# Flightcontroller.net
KiCad netlist of a schematic drawn in EAGLE
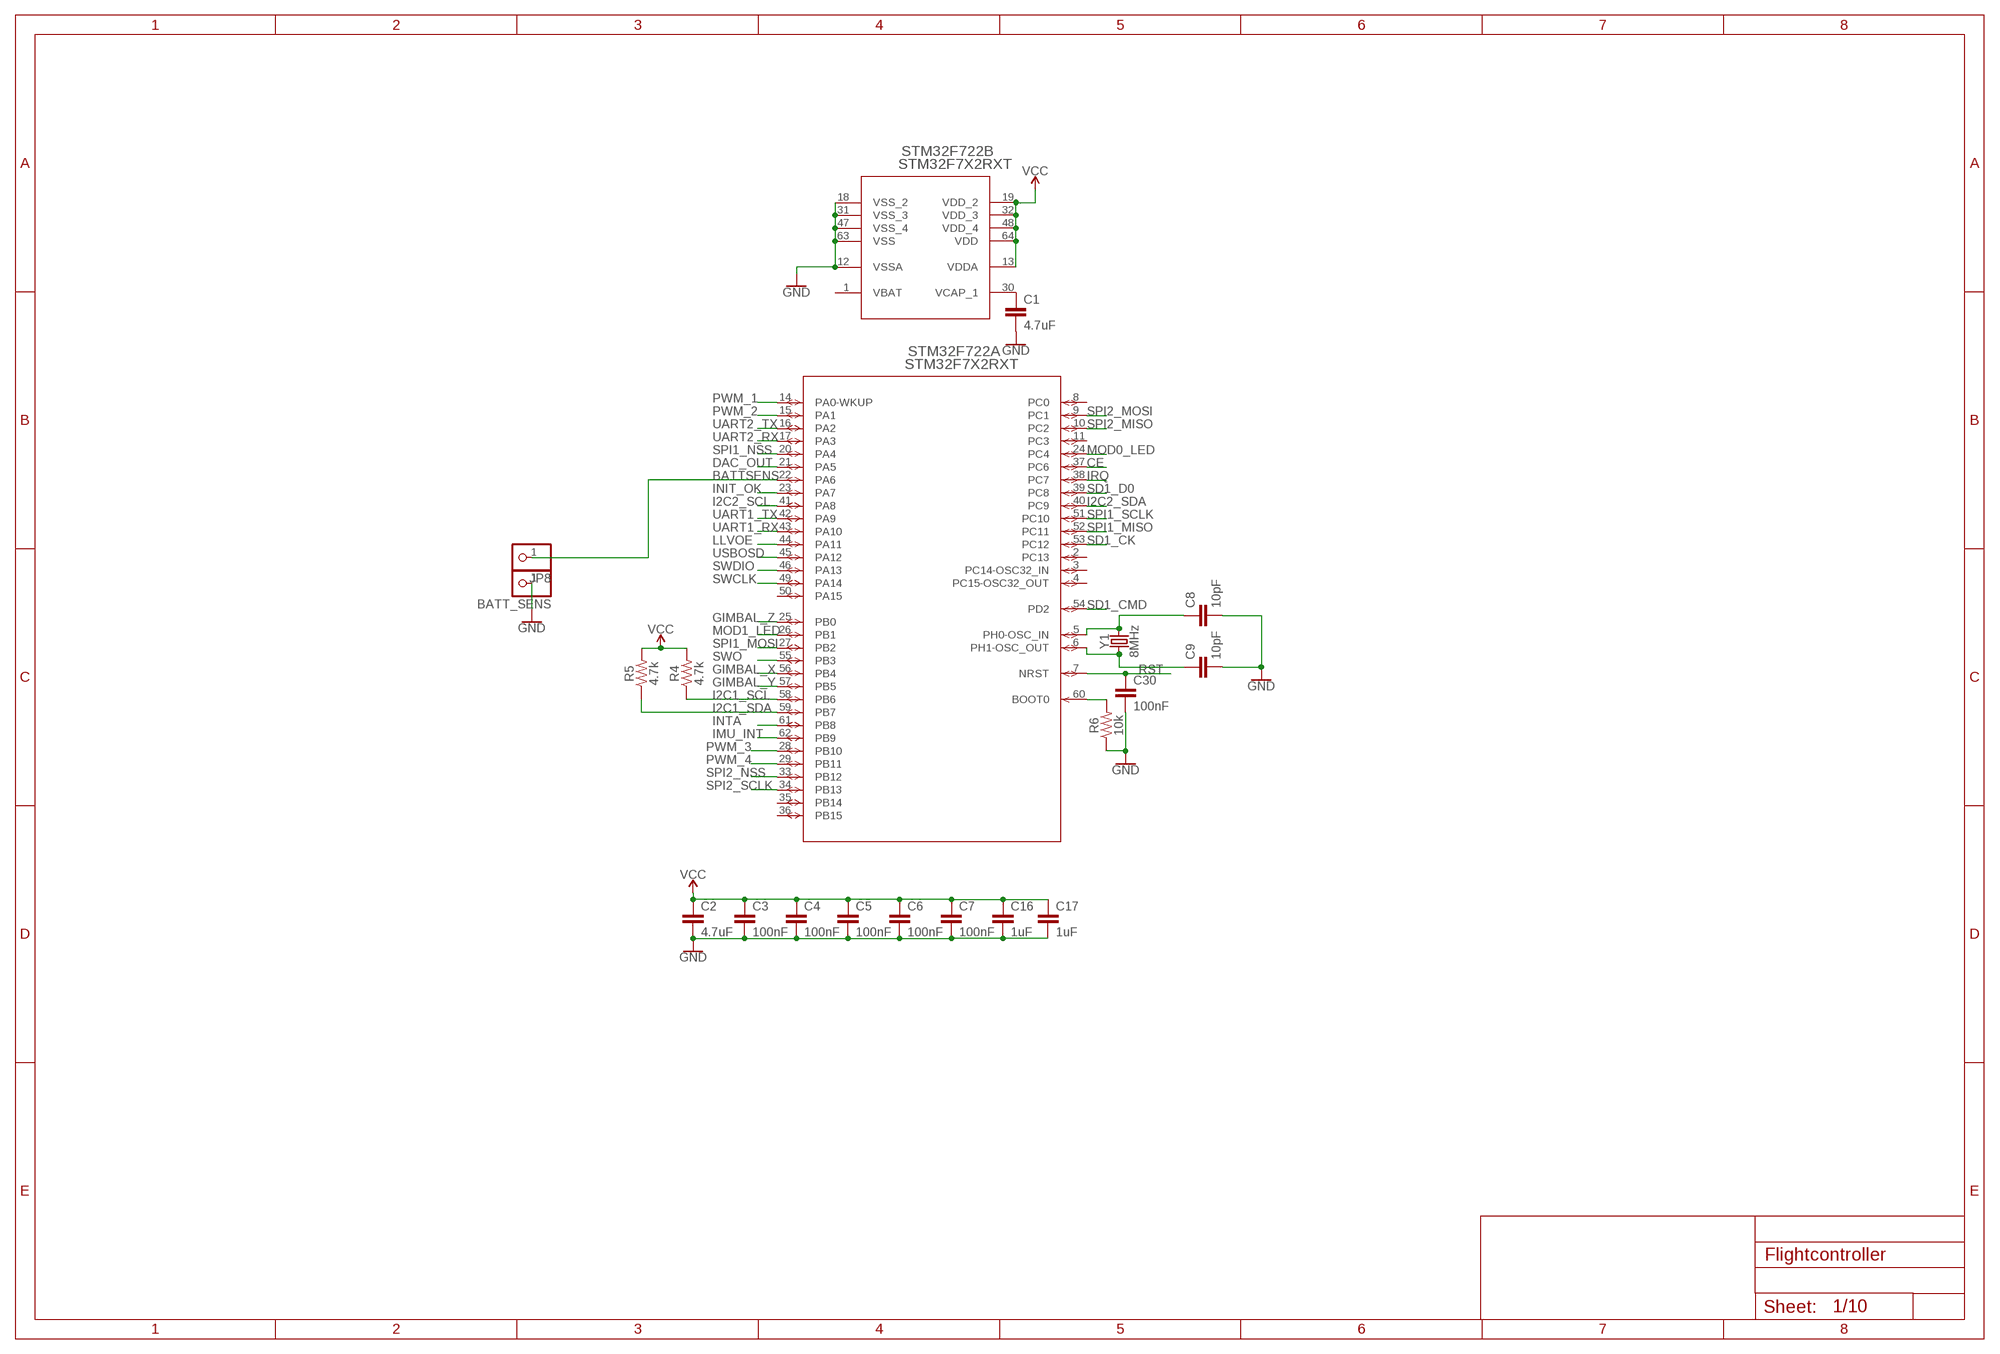
[diagram p0: schematic, sheet 1]
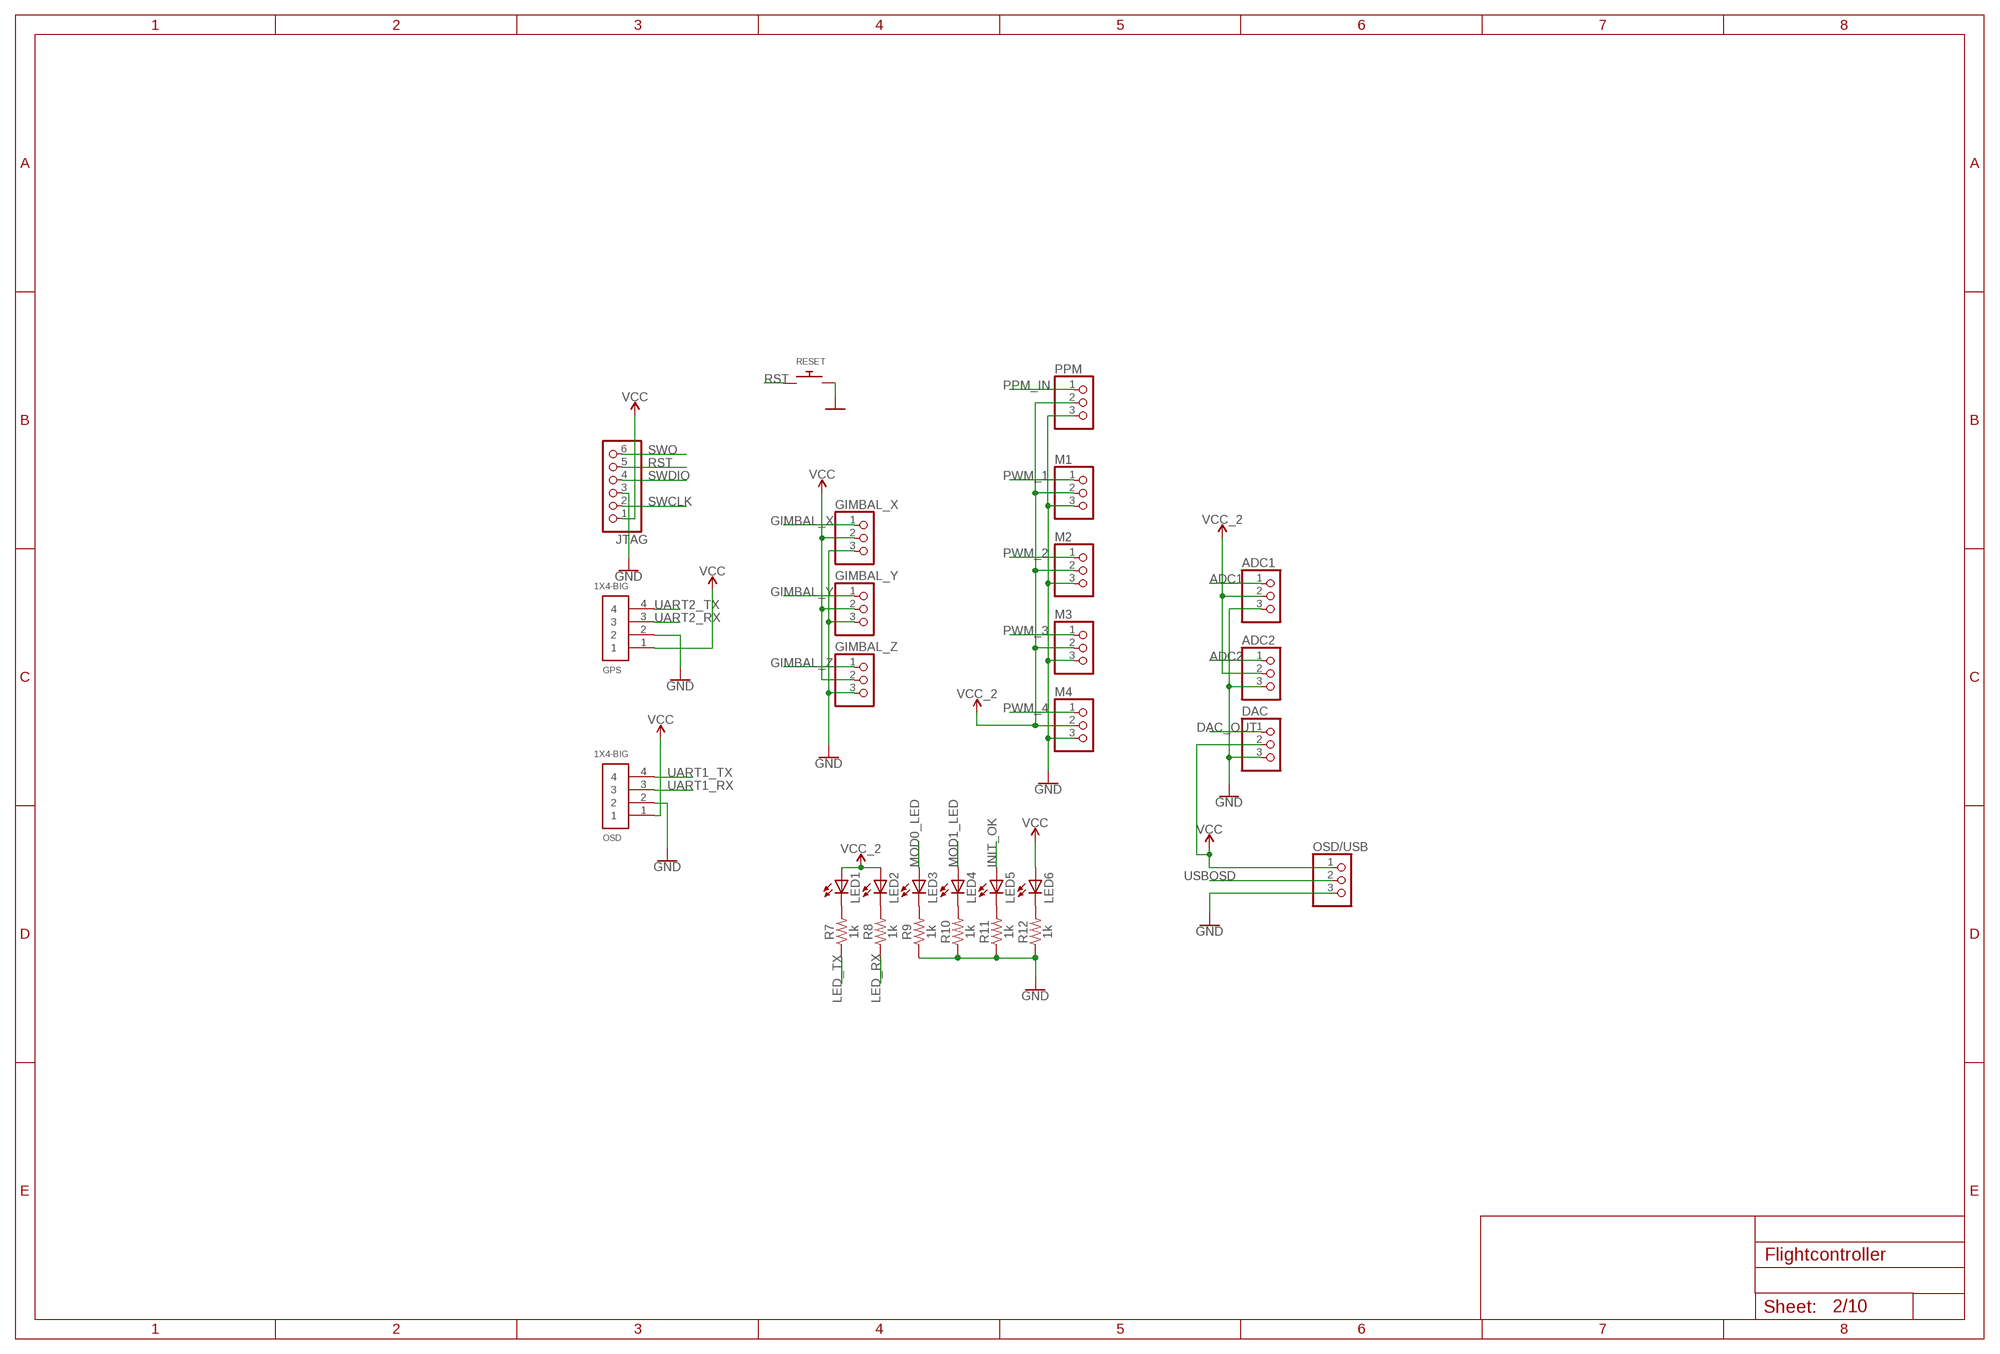
[diagram p1: schematic, sheet 2]
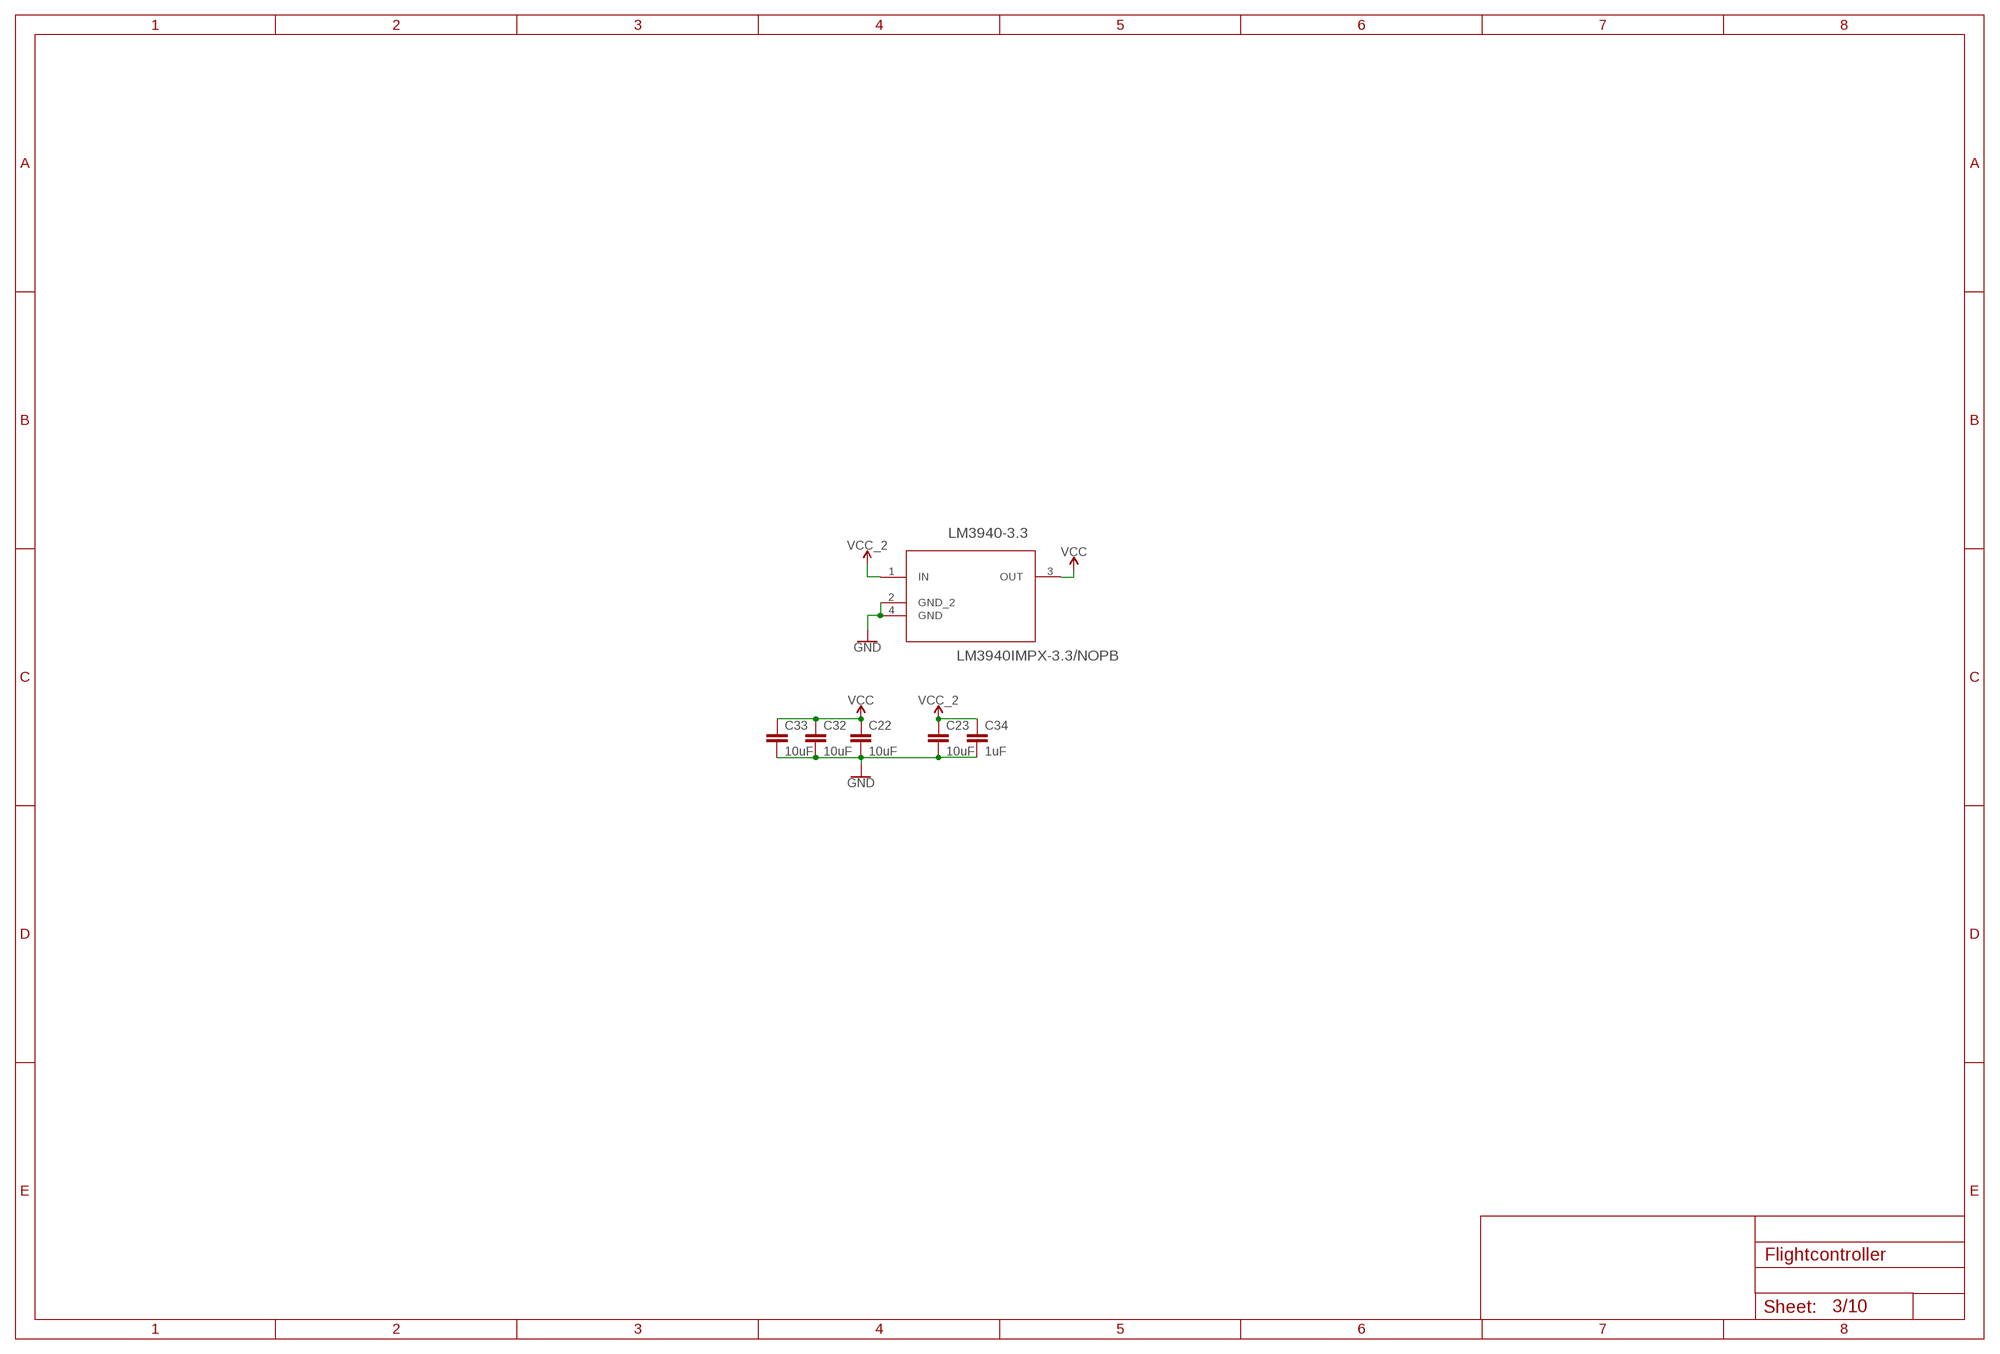
[diagram p2: schematic, sheet 3]
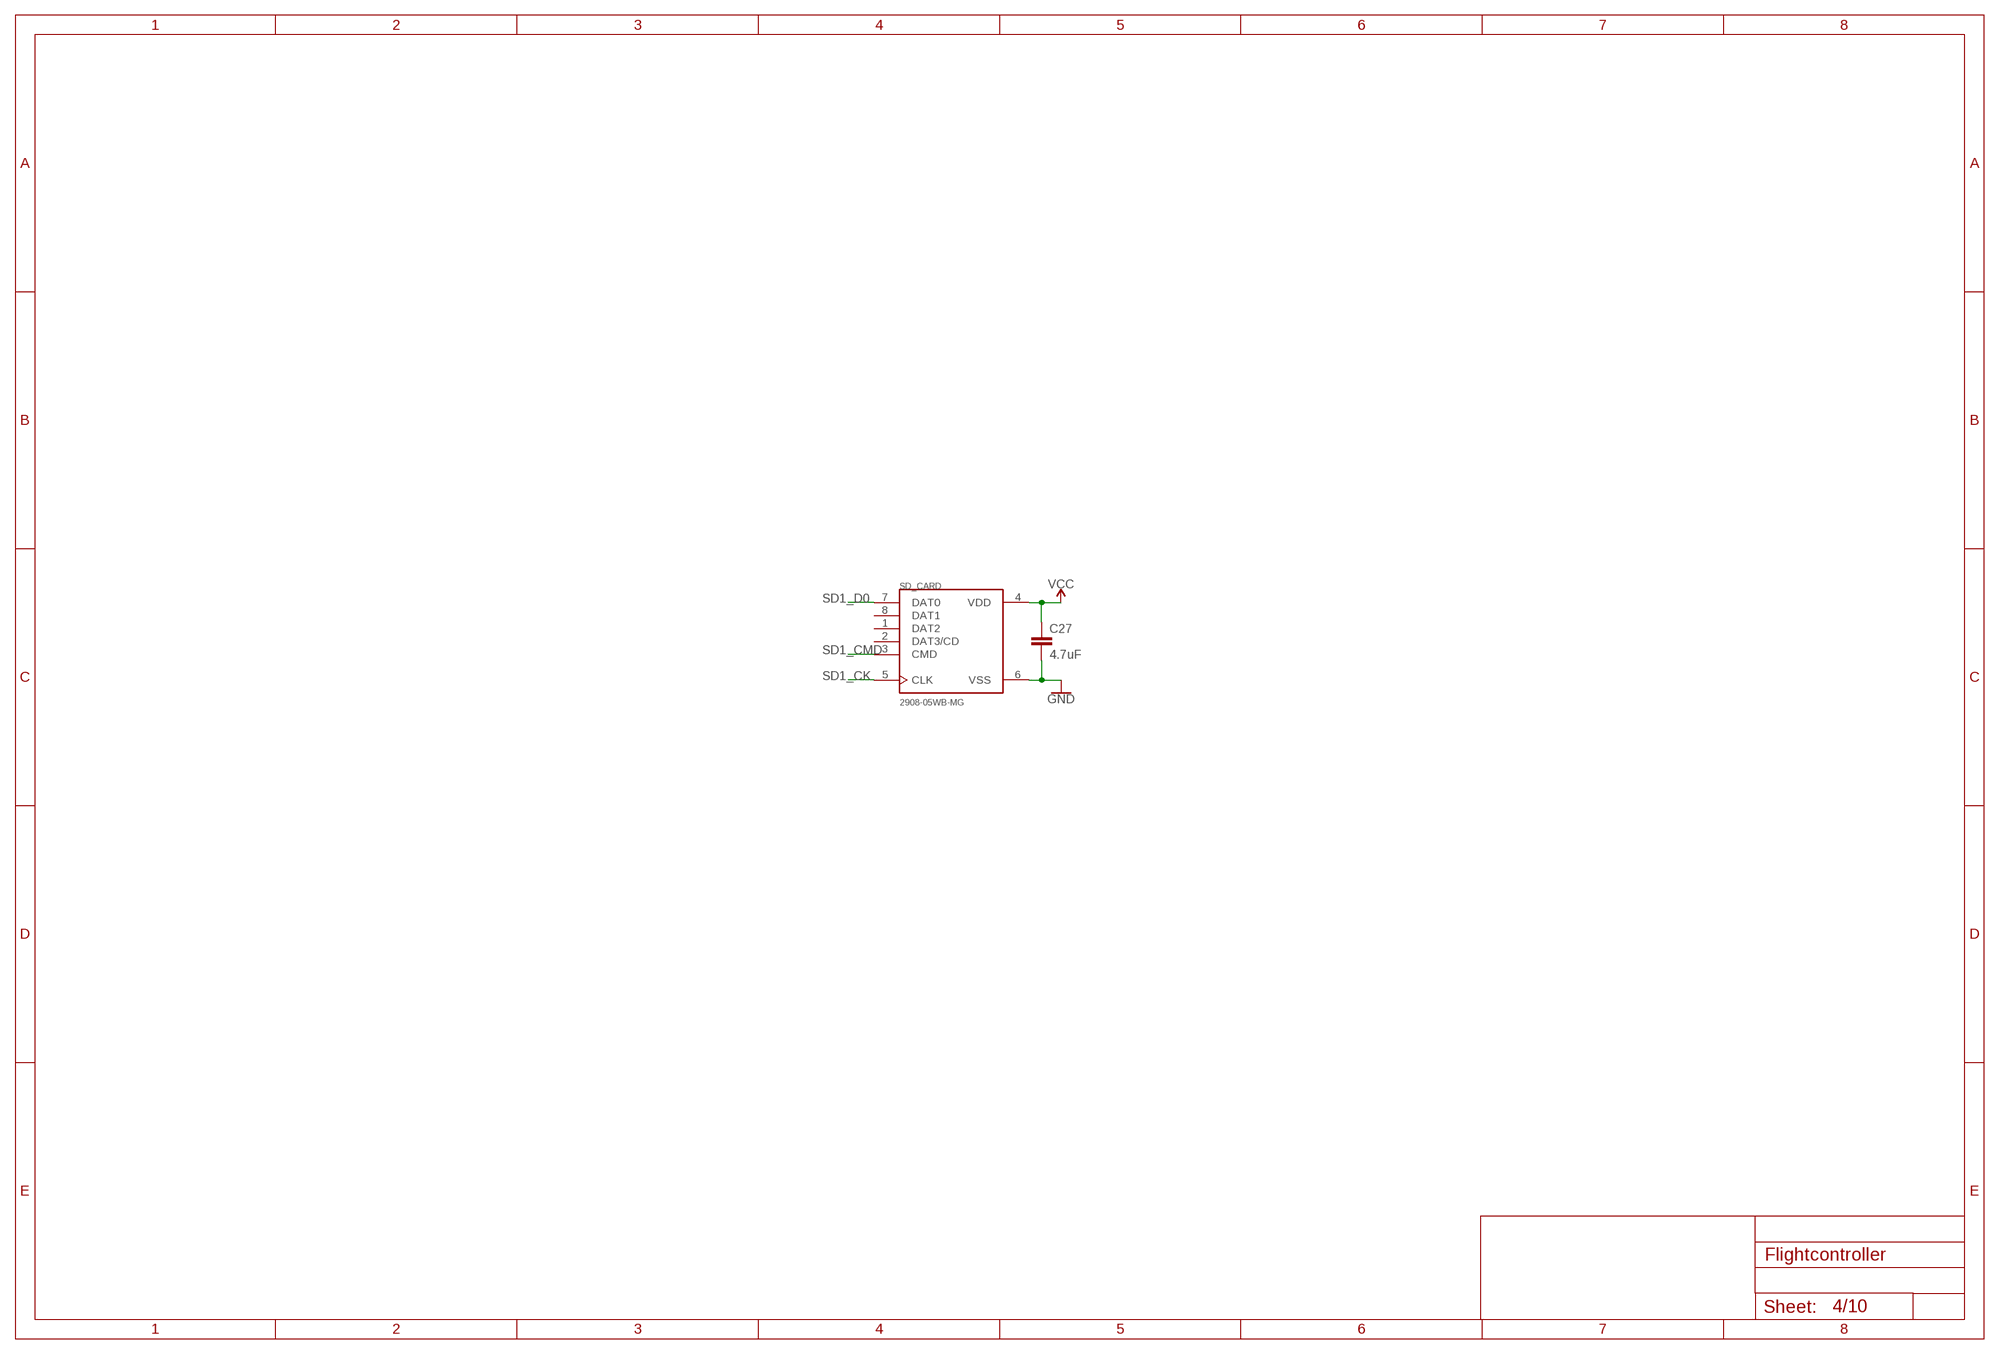
[diagram p3: schematic, sheet 4]
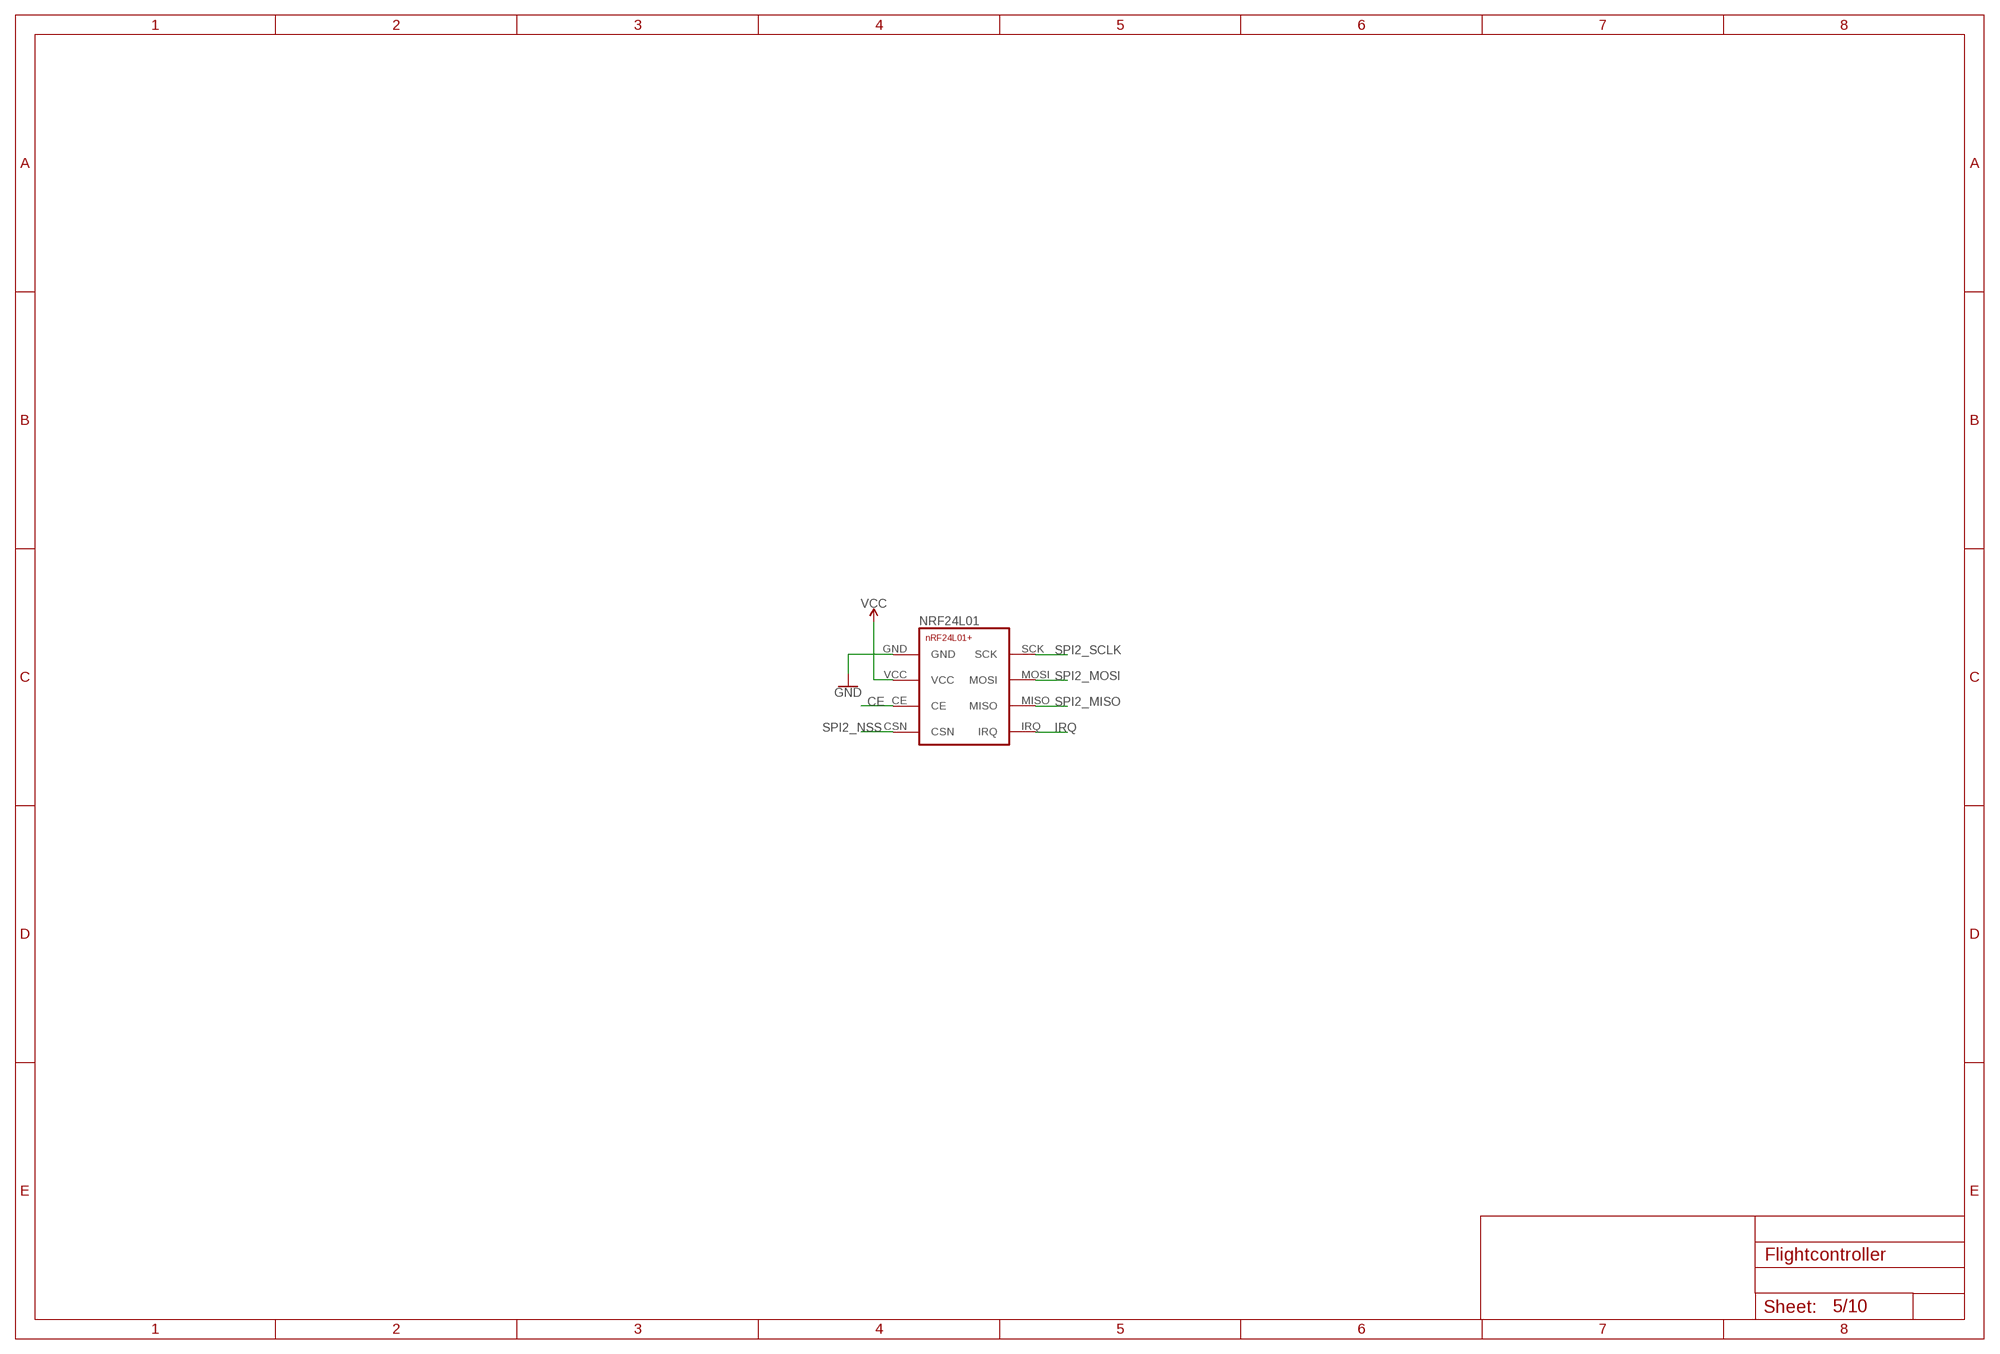
[diagram p4: schematic, sheet 5]
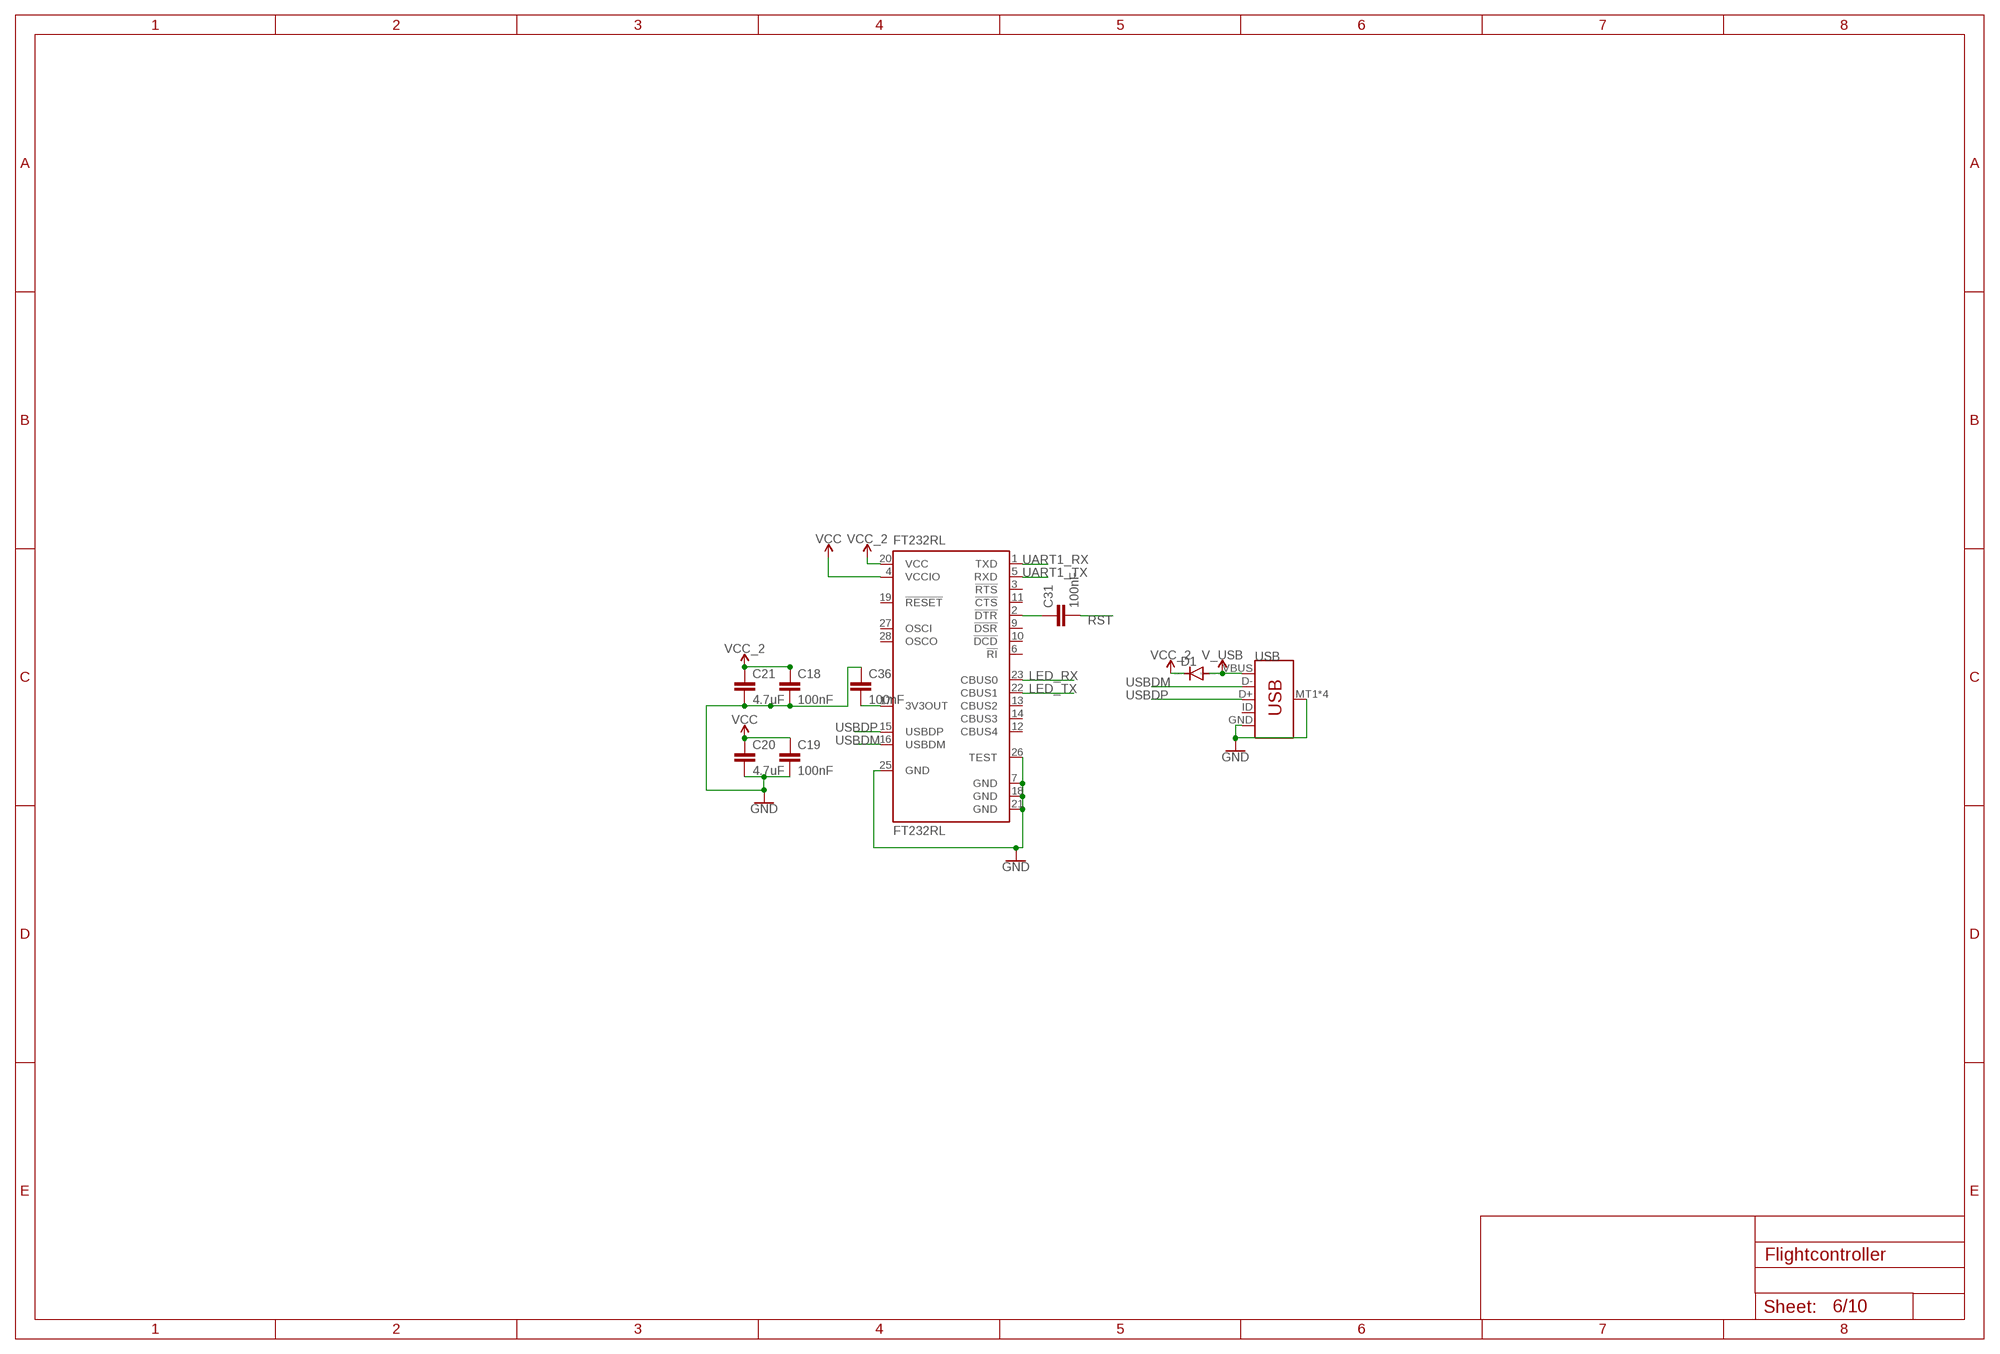
[diagram p5: schematic, sheet 6]
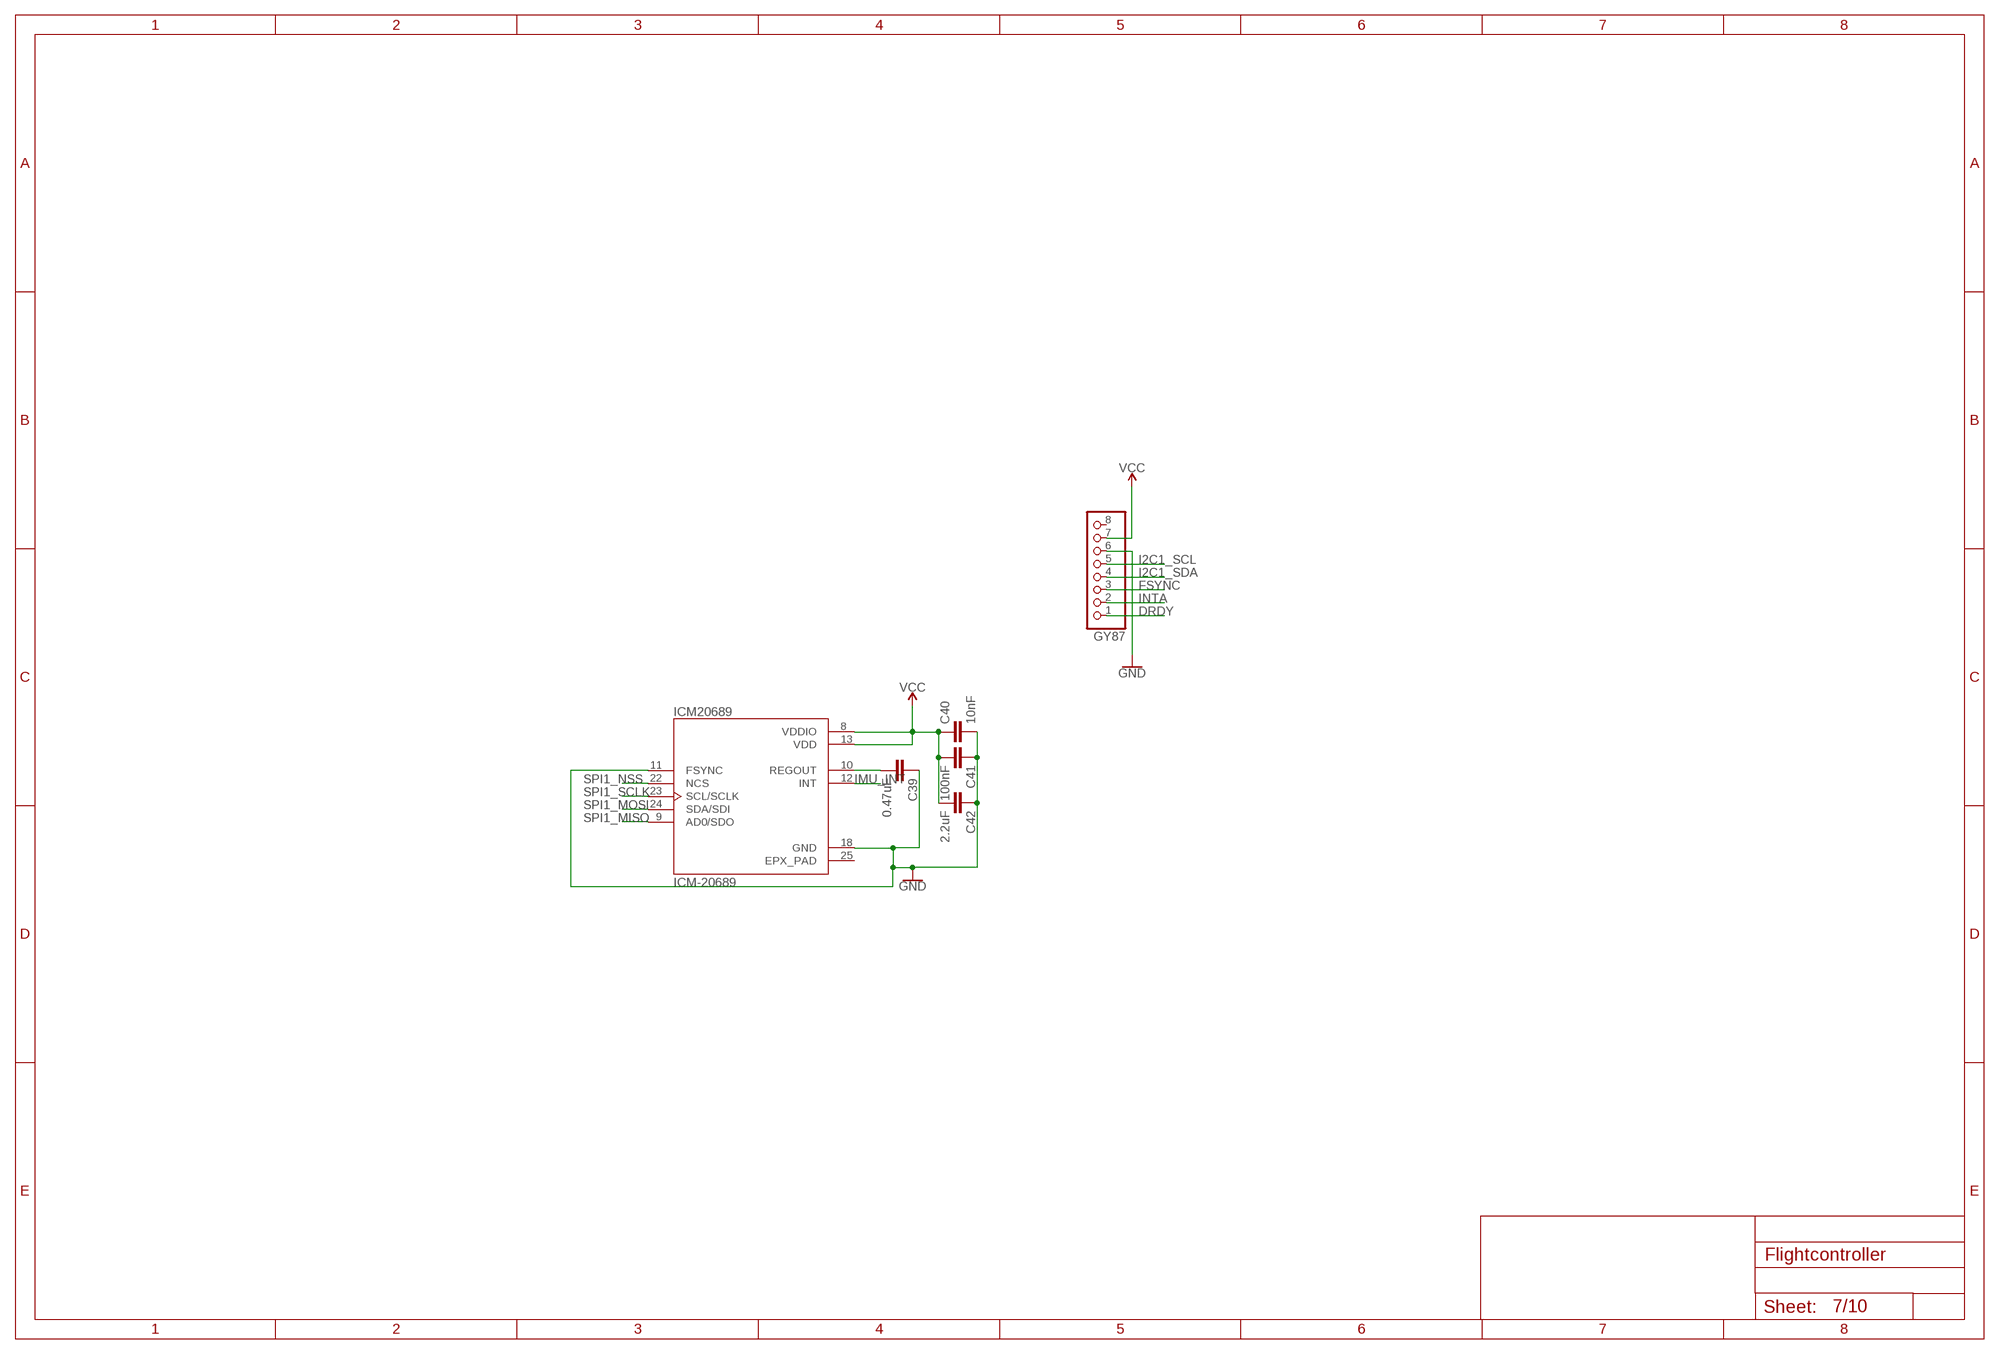
[diagram p6: schematic, sheet 7]
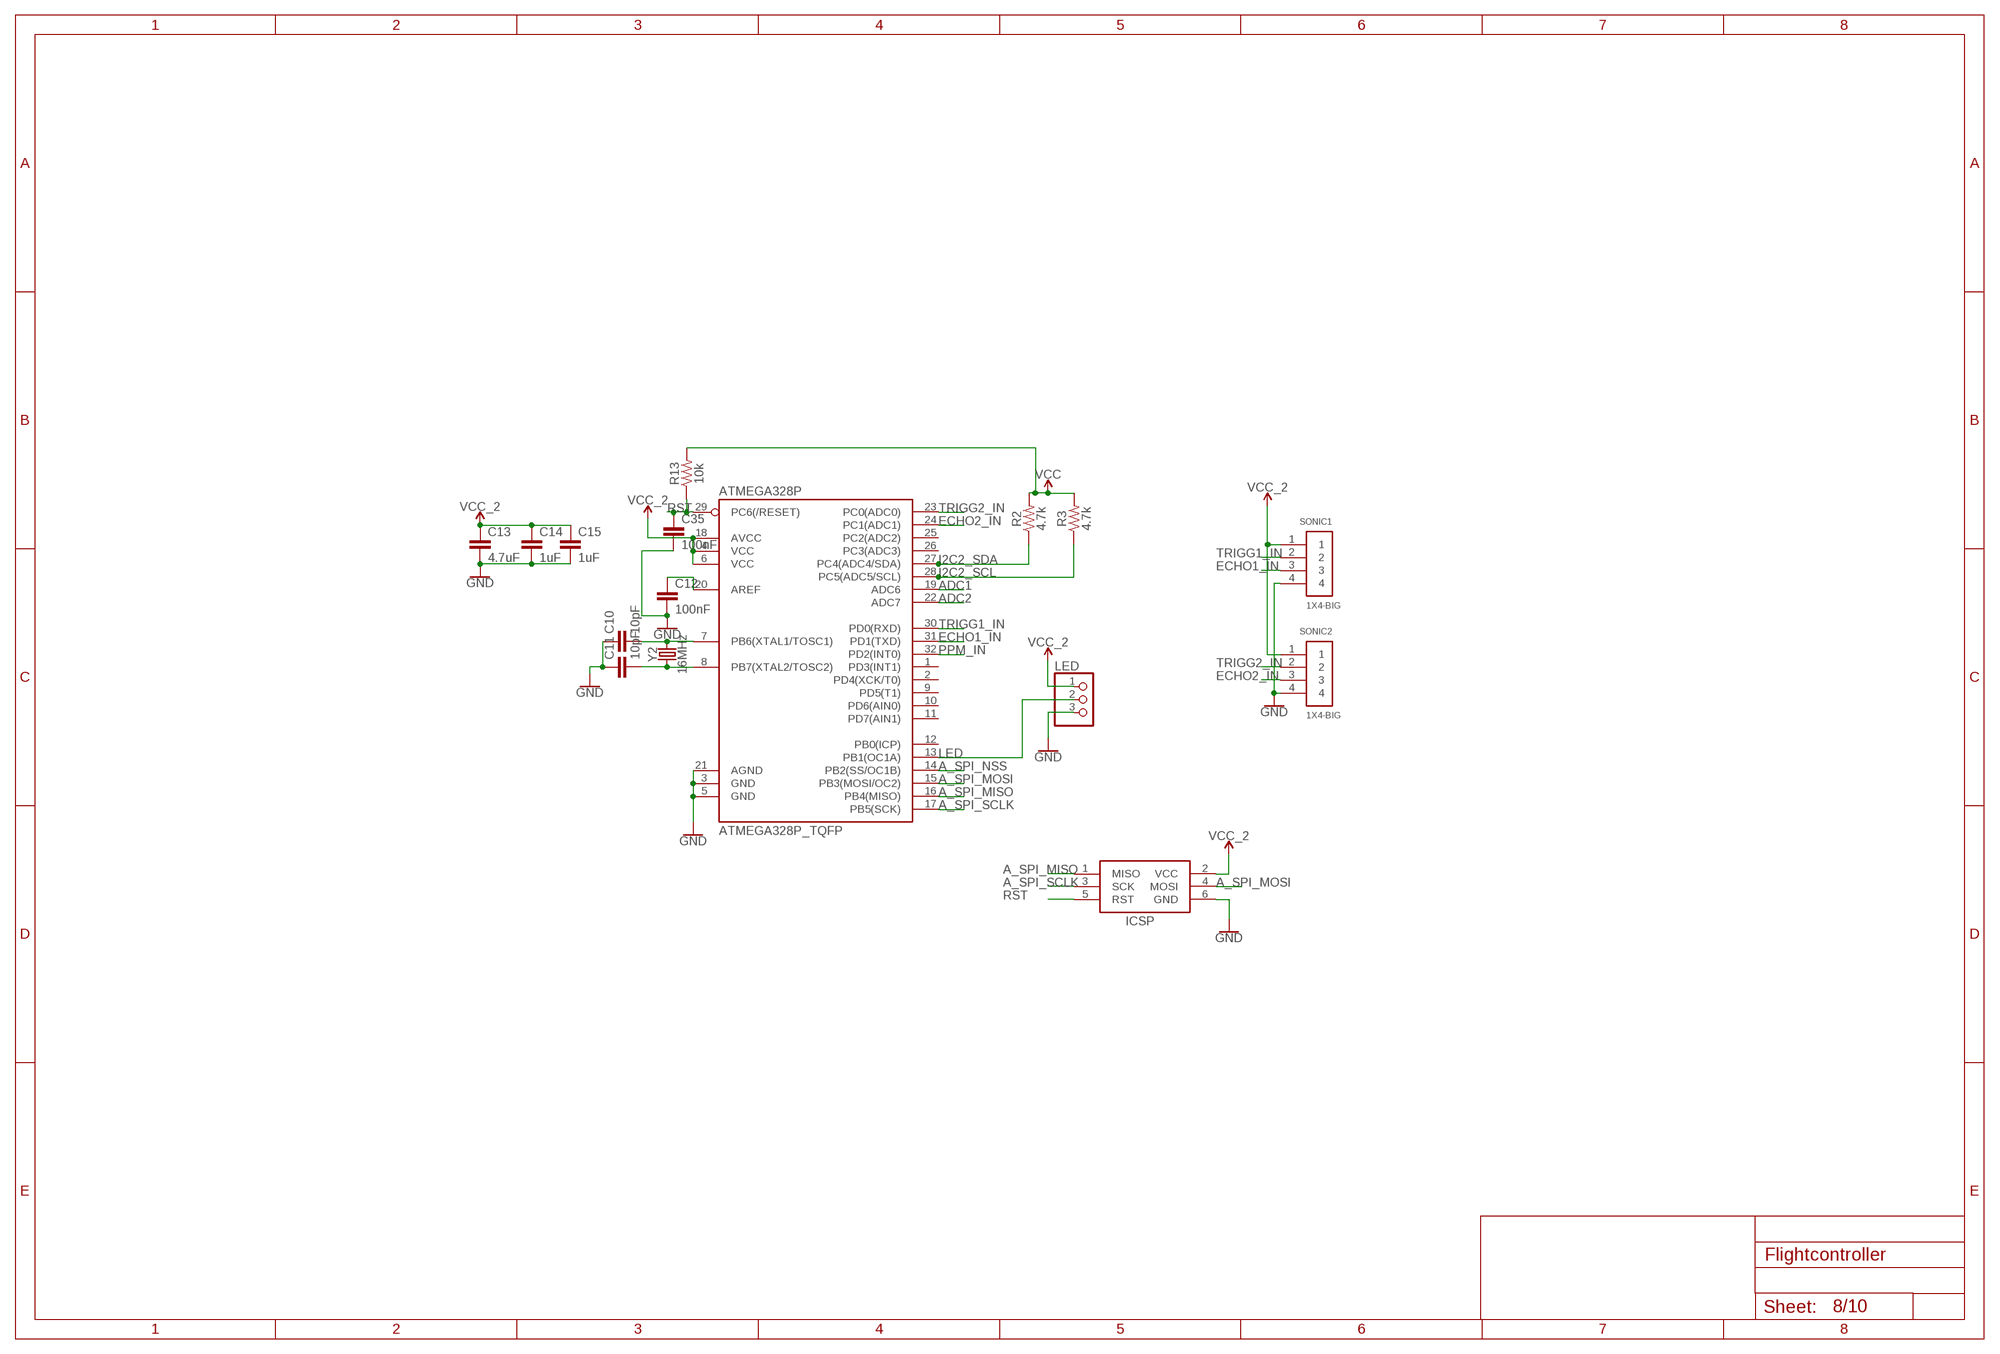
[diagram p7: schematic, sheet 8]
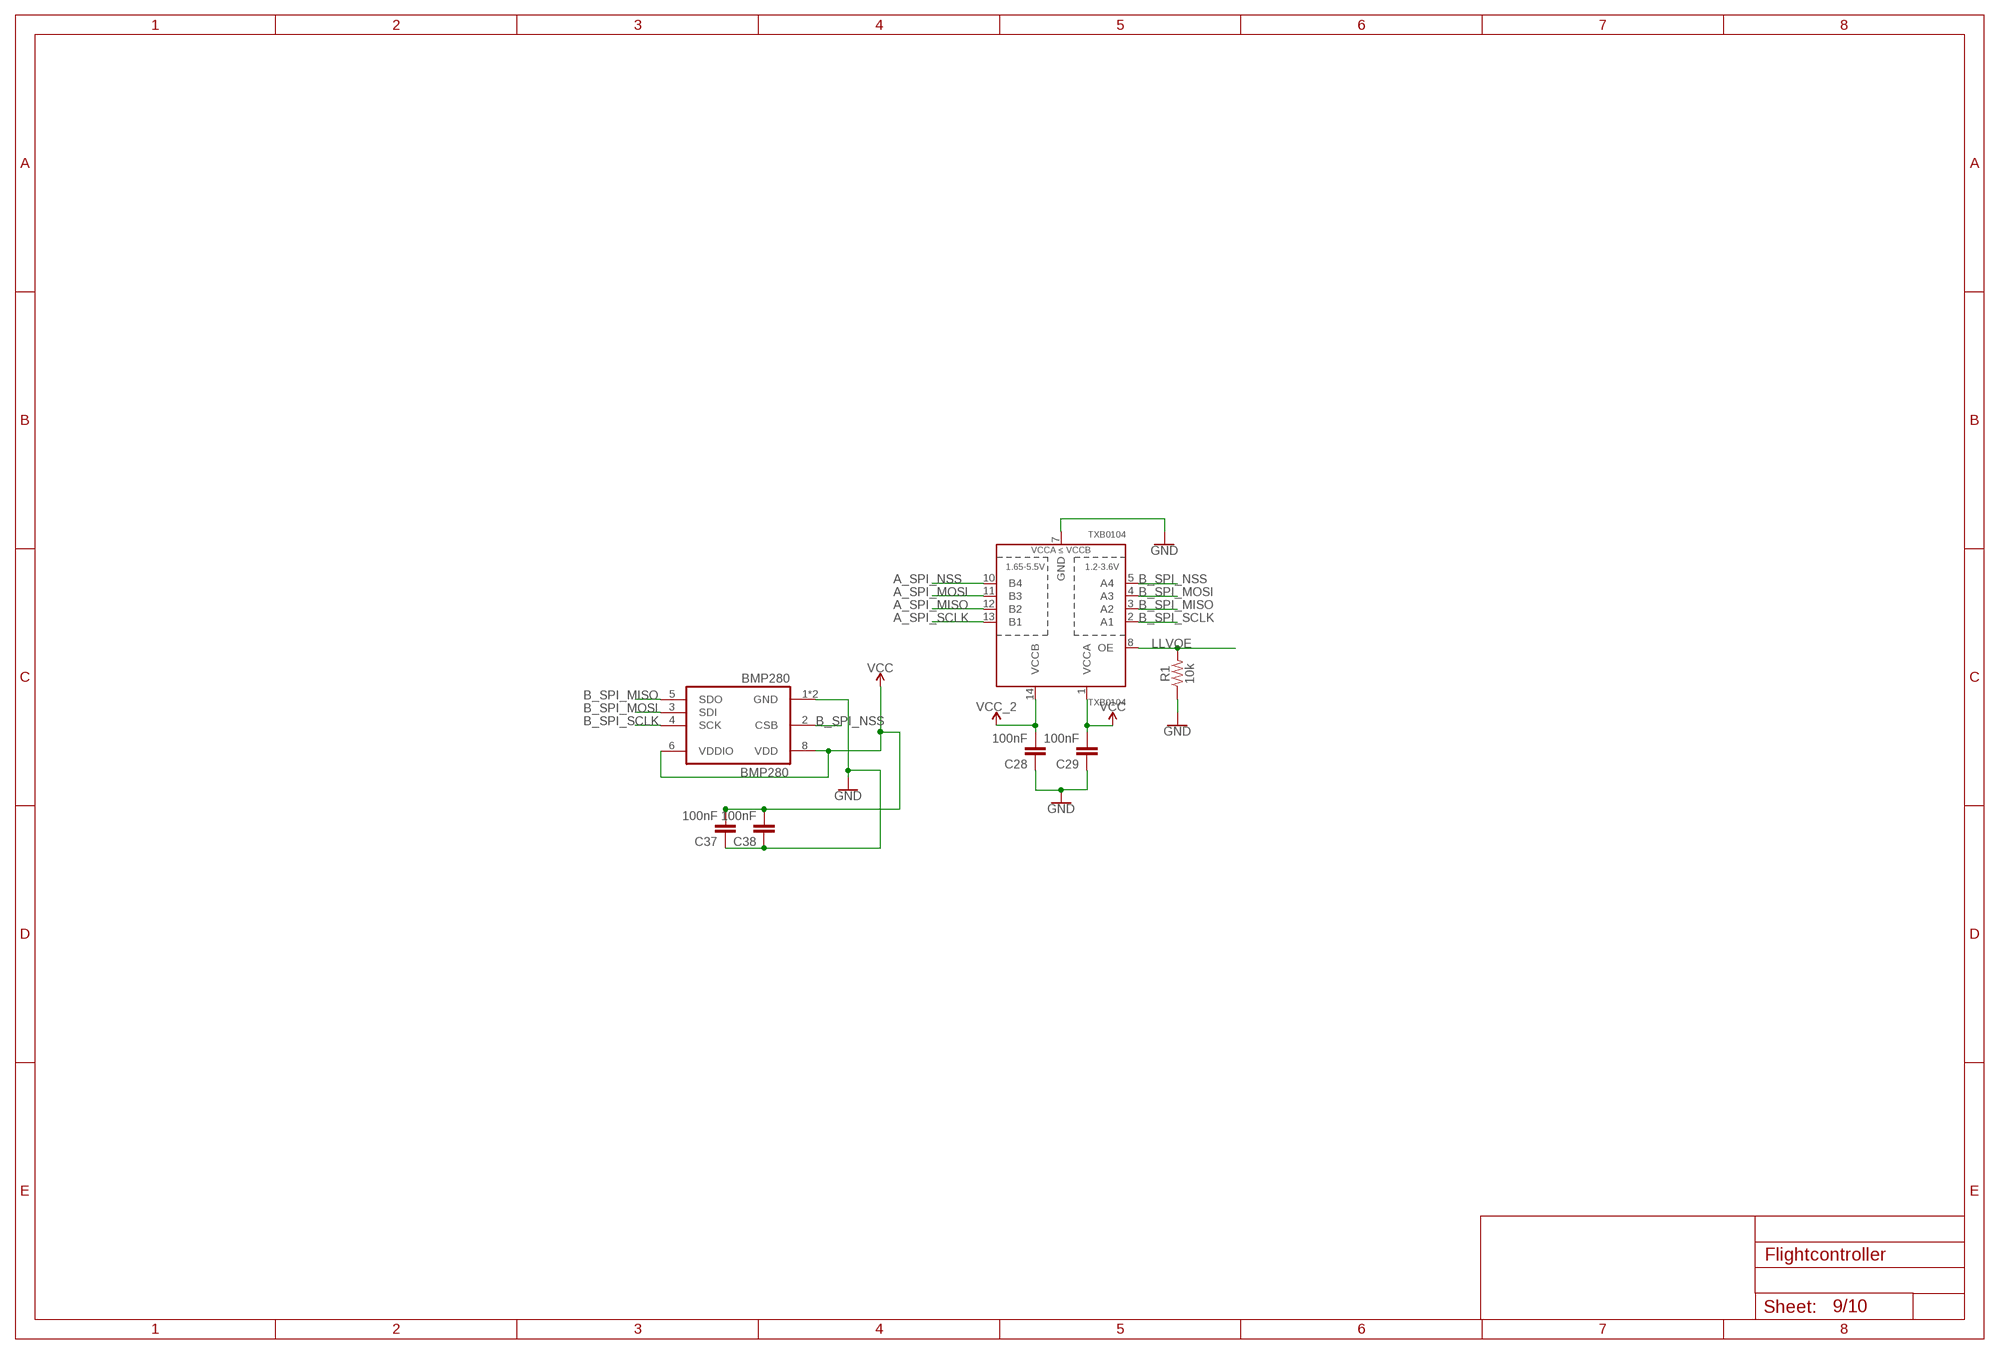
[diagram p8: schematic, sheet 9]
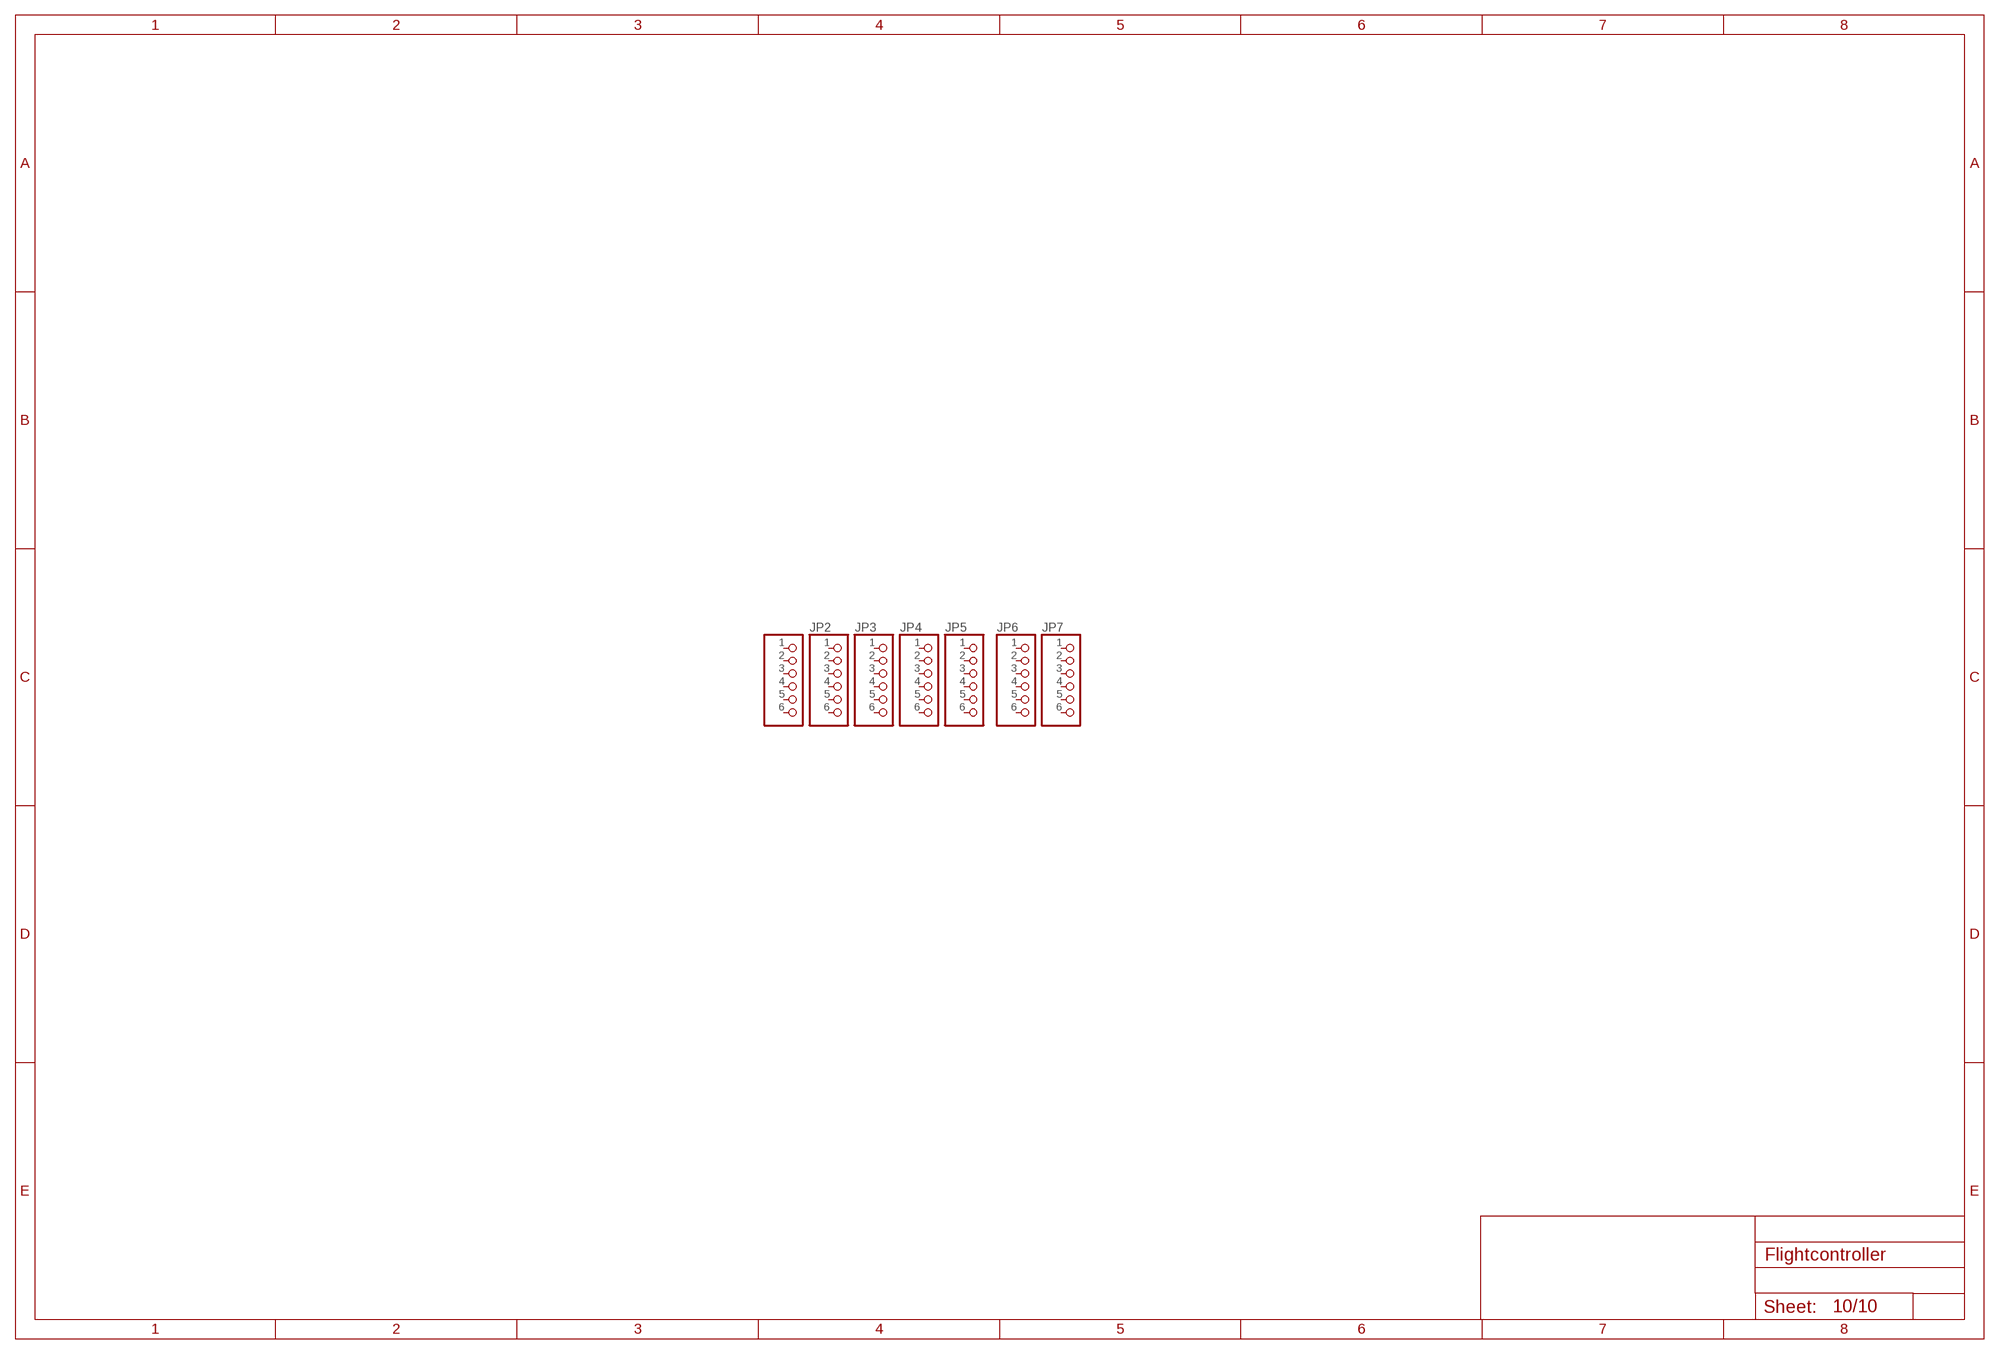
[diagram p9: schematic, sheet 10]

(export (version "E")
  (design (tool "Eeschema 10.0.6"))
  (components
    (comp (ref "BMP280")
      (value "BMP280")
      (footprint "eagle-import:BMP280")
      (libsource (lib "eagle-import") (part "BMP280"))
    )
    (comp (ref "C28")
      (value "100nF")
      (footprint "eagle-import:C0805")
      (libsource (lib "eagle-import") (part "C-EUC0805"))
    )
    (comp (ref "C29")
      (value "100nF")
      (footprint "eagle-import:C0805")
      (libsource (lib "eagle-import") (part "C-EUC0805"))
    )
    (comp (ref "C37")
      (value "100nF")
      (footprint "eagle-import:C0805")
      (libsource (lib "eagle-import") (part "C-EUC0805"))
    )
    (comp (ref "C38")
      (value "100nF")
      (footprint "eagle-import:C0805")
      (libsource (lib "eagle-import") (part "C-EUC0805"))
    )
    (comp (ref "R1")
      (value "10k")
      (footprint "eagle-import:0603")
      (libsource (lib "eagle-import") (part "10KOHM-0603-1/10W-1%"))
    )
    (comp (ref "TXB0104")
      (value "TXB0104")
      (footprint "eagle-import:SO14")
      (libsource (lib "eagle-import") (part "TXB0104PWRSOIC14"))
    )
    (comp (ref "C18")
      (value "100nF")
      (footprint "eagle-import:C0805")
      (libsource (lib "eagle-import") (part "C-EUC0805"))
    )
    (comp (ref "C19")
      (value "100nF")
      (footprint "eagle-import:C0805")
      (libsource (lib "eagle-import") (part "C-EUC0805"))
    )
    (comp (ref "C20")
      (value "4.7uF")
      (footprint "eagle-import:C0805")
      (libsource (lib "eagle-import") (part "resistor_348_C-EUC0805"))
    )
    (comp (ref "C21")
      (value "4.7uF")
      (footprint "eagle-import:C0805")
      (libsource (lib "eagle-import") (part "resistor_348_C-EUC0805"))
    )
    (comp (ref "C31")
      (value "100nF")
      (footprint "eagle-import:C0805")
      (libsource (lib "eagle-import") (part "C-EUC0805"))
    )
    (comp (ref "C36")
      (value "100nF")
      (footprint "eagle-import:C0805")
      (libsource (lib "eagle-import") (part "C-EUC0805"))
    )
    (comp (ref "D1")
      (value "DIODE-DO214BA")
      (footprint "eagle-import:DO214BA")
      (libsource (lib "eagle-import") (part "DIODE-DO214BA"))
    )
    (comp (ref "FT232RL")
      (value "FT232RL")
      (footprint "eagle-import:SSOP28")
      (libsource (lib "eagle-import") (part "FT232RL"))
    )
    (comp (ref "USB")
      (value "USB_MICRO-B_SMT")
      (footprint "eagle-import:USB-MICROB")
      (libsource (lib "eagle-import") (part "USB_MICRO-B_SMT"))
    )
    (comp (ref "C39")
      (value "0.47uF")
      (footprint "eagle-import:C0805")
      (libsource (lib "eagle-import") (part "C-EUC0805"))
    )
    (comp (ref "C40")
      (value "10nF")
      (footprint "eagle-import:C0805")
      (libsource (lib "eagle-import") (part "C-EUC0805"))
    )
    (comp (ref "C41")
      (value "100nF")
      (footprint "eagle-import:C0805")
      (libsource (lib "eagle-import") (part "C-EUC0805"))
    )
    (comp (ref "C42")
      (value "2.2uF")
      (footprint "eagle-import:C0805")
      (libsource (lib "eagle-import") (part "C-EUC0805"))
    )
    (comp (ref "GY87")
      (value "PINHD-1X8CLEANBIG")
      (footprint "eagle-import:1X08-CLEANBIG")
      (libsource (lib "eagle-import") (part "PINHD-1X8CLEANBIG"))
    )
    (comp (ref "ICM20689")
      (value "ICM-20689")
      (footprint "eagle-import:QFN50P400X400X95-25N")
      (fields (field (name "MF") "TDK InvenSense"))
      (libsource (lib "eagle-import") (part "ICM-20689"))
    )
    (comp (ref "NRF24L01")
      (value "NRF24L01+")
      (footprint "eagle-import:NRF24L01+")
      (libsource (lib "eagle-import") (part "NRF24L01+"))
    )
    (comp (ref "JP1")
      (value "PINHD-1X6")
      (footprint "eagle-import:1X06")
      (libsource (lib "eagle-import") (part "PINHD-1X6"))
    )
    (comp (ref "JP2")
      (value "PINHD-1X6")
      (footprint "eagle-import:1X06")
      (libsource (lib "eagle-import") (part "PINHD-1X6"))
    )
    (comp (ref "JP3")
      (value "PINHD-1X6")
      (footprint "eagle-import:1X06")
      (libsource (lib "eagle-import") (part "PINHD-1X6"))
    )
    (comp (ref "JP4")
      (value "PINHD-1X6")
      (footprint "eagle-import:1X06")
      (libsource (lib "eagle-import") (part "PINHD-1X6"))
    )
    (comp (ref "JP5")
      (value "PINHD-1X6")
      (footprint "eagle-import:1X06")
      (libsource (lib "eagle-import") (part "PINHD-1X6"))
    )
    (comp (ref "JP6")
      (value "PINHD-1X6")
      (footprint "eagle-import:1X06")
      (libsource (lib "eagle-import") (part "PINHD-1X6"))
    )
    (comp (ref "JP7")
      (value "PINHD-1X6")
      (footprint "eagle-import:1X06")
      (libsource (lib "eagle-import") (part "PINHD-1X6"))
    )
    (comp (ref "ATMEGA328P")
      (value "ATMEGA328P_TQFP")
      (footprint "eagle-import:TQFP32-08")
      (libsource (lib "eagle-import") (part "ATMEGA328P_TQFP"))
    )
    (comp (ref "C10")
      (value "10pF")
      (footprint "eagle-import:C0805")
      (libsource (lib "eagle-import") (part "C-EUC0805"))
    )
    (comp (ref "C11")
      (value "10pF")
      (footprint "eagle-import:C0805")
      (libsource (lib "eagle-import") (part "C-EUC0805"))
    )
    (comp (ref "C12")
      (value "100nF")
      (footprint "eagle-import:C0805")
      (libsource (lib "eagle-import") (part "C-EUC0805"))
    )
    (comp (ref "C13")
      (value "4.7uF")
      (footprint "eagle-import:C0805")
      (libsource (lib "eagle-import") (part "resistor_348_C-EUC0805"))
    )
    (comp (ref "C14")
      (value "1uF")
      (footprint "eagle-import:C0805")
      (libsource (lib "eagle-import") (part "C-EUC0805"))
    )
    (comp (ref "C15")
      (value "1uF")
      (footprint "eagle-import:C0805")
      (libsource (lib "eagle-import") (part "C-EUC0805"))
    )
    (comp (ref "C35")
      (value "100nF")
      (footprint "eagle-import:C0805")
      (libsource (lib "eagle-import") (part "C-EUC0805"))
    )
    (comp (ref "ICSP")
      (value "AVRISP-6")
      (footprint "eagle-import:AVRISP")
      (libsource (lib "eagle-import") (part "AVRISP-6"))
    )
    (comp (ref "LED")
      (value "PINHD-1X3")
      (footprint "eagle-import:1X03")
      (libsource (lib "eagle-import") (part "PINHD-1X3"))
    )
    (comp (ref "R2")
      (value "4.7k")
      (footprint "eagle-import:0603")
      (libsource (lib "eagle-import") (part "4.7KOHM-0603-1/10W-1%"))
    )
    (comp (ref "R3")
      (value "4.7k")
      (footprint "eagle-import:0603")
      (libsource (lib "eagle-import") (part "4.7KOHM-0603-1/10W-1%"))
    )
    (comp (ref "R13")
      (value "10k")
      (footprint "eagle-import:0603")
      (libsource (lib "eagle-import") (part "4.7KOHM-0603-1/10W-1%"))
    )
    (comp (ref "SONIC1")
      (value "1X4-BIG")
      (footprint "eagle-import:1X04-BIG")
      (libsource (lib "eagle-import") (part "1X4-BIG"))
    )
    (comp (ref "SONIC2")
      (value "1X4-BIG")
      (footprint "eagle-import:1X04-BIG")
      (libsource (lib "eagle-import") (part "1X4-BIG"))
    )
    (comp (ref "Y2")
      (value "16MHz")
      (footprint "eagle-import:CRYSTAL-SMD-5X3.2-4PAD")
      (libsource (lib "eagle-import") (part "CRYSTAL-16MHZSMD-5X3.2"))
    )
    (comp (ref "C22")
      (value "10uF")
      (footprint "eagle-import:C0805")
      (libsource (lib "eagle-import") (part "C-EUC0805"))
    )
    (comp (ref "C23")
      (value "10uF")
      (footprint "eagle-import:C0805")
      (libsource (lib "eagle-import") (part "C-EUC0805"))
    )
    (comp (ref "C32")
      (value "10uF")
      (footprint "eagle-import:C0805")
      (libsource (lib "eagle-import") (part "C-EUC0805"))
    )
    (comp (ref "C33")
      (value "10uF")
      (footprint "eagle-import:C0805")
      (libsource (lib "eagle-import") (part "C-EUC0805"))
    )
    (comp (ref "C34")
      (value "1uF")
      (footprint "eagle-import:C0805")
      (libsource (lib "eagle-import") (part "C-EUC0805"))
    )
    (comp (ref "LM3940-3.3")
      (value "LM3940IMPX-3.3/NOPB")
      (footprint "eagle-import:SOT230P696X180-4N")
      (fields (field (name "MF") "Texas Instruments"))
      (libsource (lib "eagle-import") (part "LM3940IMPX-3.3/NOPB"))
    )
    (comp (ref "ADC1")
      (value "PINHD-1X3")
      (footprint "eagle-import:1X03")
      (libsource (lib "eagle-import") (part "PINHD-1X3"))
    )
    (comp (ref "ADC2")
      (value "PINHD-1X3")
      (footprint "eagle-import:1X03")
      (libsource (lib "eagle-import") (part "PINHD-1X3"))
    )
    (comp (ref "DAC")
      (value "PINHD-1X3")
      (footprint "eagle-import:1X03")
      (libsource (lib "eagle-import") (part "PINHD-1X3"))
    )
    (comp (ref "GIMBAL_X")
      (value "PINHD-1X3")
      (footprint "eagle-import:1X03")
      (libsource (lib "eagle-import") (part "PINHD-1X3"))
    )
    (comp (ref "GIMBAL_Y")
      (value "PINHD-1X3")
      (footprint "eagle-import:1X03")
      (libsource (lib "eagle-import") (part "PINHD-1X3"))
    )
    (comp (ref "GIMBAL_Z")
      (value "PINHD-1X3")
      (footprint "eagle-import:1X03")
      (libsource (lib "eagle-import") (part "PINHD-1X3"))
    )
    (comp (ref "GPS")
      (value "1X4-BIG")
      (footprint "eagle-import:1X04-BIG")
      (libsource (lib "eagle-import") (part "1X4-BIG"))
    )
    (comp (ref "JTAG")
      (value "PINHD-1X6")
      (footprint "eagle-import:1X06")
      (libsource (lib "eagle-import") (part "PINHD-1X6"))
    )
    (comp (ref "LED1")
      (value "LEDSMT1206")
      (footprint "eagle-import:1206")
      (libsource (lib "eagle-import") (part "LEDSMT1206"))
    )
    (comp (ref "LED2")
      (value "LEDSMT1206")
      (footprint "eagle-import:1206")
      (libsource (lib "eagle-import") (part "LEDSMT1206"))
    )
    (comp (ref "LED3")
      (value "LEDSMT1206")
      (footprint "eagle-import:1206")
      (libsource (lib "eagle-import") (part "LEDSMT1206"))
    )
    (comp (ref "LED4")
      (value "LEDSMT1206")
      (footprint "eagle-import:1206")
      (libsource (lib "eagle-import") (part "LEDSMT1206"))
    )
    (comp (ref "LED5")
      (value "LEDSMT1206")
      (footprint "eagle-import:1206")
      (libsource (lib "eagle-import") (part "LEDSMT1206"))
    )
    (comp (ref "LED6")
      (value "LEDSMT1206")
      (footprint "eagle-import:1206")
      (libsource (lib "eagle-import") (part "LEDSMT1206"))
    )
    (comp (ref "M1")
      (value "PINHD-1X3")
      (footprint "eagle-import:1X03")
      (libsource (lib "eagle-import") (part "PINHD-1X3"))
    )
    (comp (ref "M2")
      (value "PINHD-1X3")
      (footprint "eagle-import:1X03")
      (libsource (lib "eagle-import") (part "PINHD-1X3"))
    )
    (comp (ref "M3")
      (value "PINHD-1X3")
      (footprint "eagle-import:1X03")
      (libsource (lib "eagle-import") (part "PINHD-1X3"))
    )
    (comp (ref "M4")
      (value "PINHD-1X3")
      (footprint "eagle-import:1X03")
      (libsource (lib "eagle-import") (part "PINHD-1X3"))
    )
    (comp (ref "OSD")
      (value "1X4-BIG")
      (footprint "eagle-import:1X04-BIG")
      (libsource (lib "eagle-import") (part "1X4-BIG"))
    )
    (comp (ref "OSD/USB")
      (value "PINHD-1X3")
      (footprint "eagle-import:1X03")
      (libsource (lib "eagle-import") (part "PINHD-1X3"))
    )
    (comp (ref "PPM")
      (value "PINHD-1X3")
      (footprint "eagle-import:1X03")
      (libsource (lib "eagle-import") (part "PINHD-1X3"))
    )
    (comp (ref "R7")
      (value "1k")
      (footprint "eagle-import:0603")
      (libsource (lib "eagle-import") (part "10KOHM-0603-1/10W-1%"))
    )
    (comp (ref "R8")
      (value "1k")
      (footprint "eagle-import:0603")
      (libsource (lib "eagle-import") (part "10KOHM-0603-1/10W-1%"))
    )
    (comp (ref "R9")
      (value "1k")
      (footprint "eagle-import:0603")
      (libsource (lib "eagle-import") (part "10KOHM-0603-1/10W-1%"))
    )
    (comp (ref "R10")
      (value "1k")
      (footprint "eagle-import:0603")
      (libsource (lib "eagle-import") (part "10KOHM-0603-1/10W-1%"))
    )
    (comp (ref "R11")
      (value "1k")
      (footprint "eagle-import:0603")
      (libsource (lib "eagle-import") (part "10KOHM-0603-1/10W-1%"))
    )
    (comp (ref "R12")
      (value "1k")
      (footprint "eagle-import:0603")
      (libsource (lib "eagle-import") (part "10KOHM-0603-1/10W-1%"))
    )
    (comp (ref "RESET")
      (value "SWITCH_PUSHBUTTONC&K_KSS")
      (footprint "eagle-import:BTN_CK_KSS")
      (libsource (lib "eagle-import") (part "SWITCH_PUSHBUTTONC&K_KSS"))
    )
    (comp (ref "BATT_SENS")
      (value "PINHD-1X1")
      (footprint "eagle-import:1X01")
      (libsource (lib "eagle-import") (part "PINHD-1X1"))
    )
    (comp (ref "C1")
      (value "4.7uF")
      (footprint "eagle-import:C0805")
      (libsource (lib "eagle-import") (part "resistor_348_C-EUC0805"))
    )
    (comp (ref "C2")
      (value "4.7uF")
      (footprint "eagle-import:C0805")
      (libsource (lib "eagle-import") (part "resistor_348_C-EUC0805"))
    )
    (comp (ref "C3")
      (value "100nF")
      (footprint "eagle-import:C0805")
      (libsource (lib "eagle-import") (part "C-EUC0805"))
    )
    (comp (ref "C4")
      (value "100nF")
      (footprint "eagle-import:C0805")
      (libsource (lib "eagle-import") (part "C-EUC0805"))
    )
    (comp (ref "C5")
      (value "100nF")
      (footprint "eagle-import:C0805")
      (libsource (lib "eagle-import") (part "C-EUC0805"))
    )
    (comp (ref "C6")
      (value "100nF")
      (footprint "eagle-import:C0805")
      (libsource (lib "eagle-import") (part "C-EUC0805"))
    )
    (comp (ref "C7")
      (value "100nF")
      (footprint "eagle-import:C0805")
      (libsource (lib "eagle-import") (part "C-EUC0805"))
    )
    (comp (ref "C8")
      (value "10pF")
      (footprint "eagle-import:C0805")
      (libsource (lib "eagle-import") (part "C-EUC0805"))
    )
    (comp (ref "C9")
      (value "10pF")
      (footprint "eagle-import:C0805")
      (libsource (lib "eagle-import") (part "C-EUC0805"))
    )
    (comp (ref "C16")
      (value "1uF")
      (footprint "eagle-import:C0805")
      (libsource (lib "eagle-import") (part "C-EUC0805"))
    )
    (comp (ref "C17")
      (value "1uF")
      (footprint "eagle-import:C0805")
      (libsource (lib "eagle-import") (part "C-EUC0805"))
    )
    (comp (ref "C30")
      (value "100nF")
      (footprint "eagle-import:C0805")
      (libsource (lib "eagle-import") (part "C-EUC0805"))
    )
    (comp (ref "JP8")
      (value "PINHD-1X1")
      (footprint "eagle-import:1X01")
      (libsource (lib "eagle-import") (part "PINHD-1X1"))
    )
    (comp (ref "R4")
      (value "4.7k")
      (footprint "eagle-import:0603")
      (libsource (lib "eagle-import") (part "4.7KOHM-0603-1/10W-1%"))
    )
    (comp (ref "R5")
      (value "4.7k")
      (footprint "eagle-import:0603")
      (libsource (lib "eagle-import") (part "4.7KOHM-0603-1/10W-1%"))
    )
    (comp (ref "R6")
      (value "10k")
      (footprint "eagle-import:0603")
      (libsource (lib "eagle-import") (part "10KOHM-0603-1/10W-1%"))
    )
    (comp (ref "STM32F722")
      (value "STM32F7X2RXT")
      (footprint "eagle-import:LQFP64-10X10MM")
      (libsource (lib "eagle-import") (part "STM32F7X2RXT"))
    )
    (comp (ref "Y1")
      (value "8MHz")
      (footprint "eagle-import:CRYSTAL-SMD-5X3.2-4PAD")
      (libsource (lib "eagle-import") (part "CRYSTAL-8MHZSMD-5X3.2"))
    )
    (comp (ref "C27")
      (value "4.7uF")
      (footprint "eagle-import:C0805")
      (libsource (lib "eagle-import") (part "resistor_348_C-EUC0805"))
    )
    (comp (ref "SD_CARD")
      (value "2908-05WB-MG")
      (footprint "eagle-import:3M_2908-05WB-MG")
      (fields (field (name "MF") "3M"))
      (libsource (lib "eagle-import") (part "2908-05WB-MG"))
    )
  )
  (nets
    (net (code "1") (name "ADC1") (class "Default")
      (node (ref "ADC1") (pin "1") (pinfunction "1_1") (pintype "passive"))
      (node (ref "ATMEGA328P") (pin "19") (pinfunction "ADC6_19") (pintype "bidirectional"))
    )
    (net (code "2") (name "ADC2") (class "Default")
      (node (ref "ADC2") (pin "1") (pinfunction "1_1") (pintype "passive"))
      (node (ref "ATMEGA328P") (pin "22") (pinfunction "ADC7_22") (pintype "bidirectional"))
    )
    (net (code "3") (name "A_SPI_MISO") (class "Default")
      (node (ref "ATMEGA328P") (pin "16") (pinfunction "PB4(MISO)_16") (pintype "bidirectional"))
      (node (ref "ICSP") (pin "1") (pinfunction "MISO_1") (pintype "input"))
      (node (ref "TXB0104") (pin "12") (pinfunction "B2_12") (pintype "bidirectional"))
    )
    (net (code "4") (name "A_SPI_MOSI") (class "Default")
      (node (ref "ATMEGA328P") (pin "15") (pinfunction "PB3(MOSI/OC2)_15") (pintype "bidirectional"))
      (node (ref "ICSP") (pin "4") (pinfunction "MOSI_4") (pintype "output"))
      (node (ref "TXB0104") (pin "11") (pinfunction "B3_11") (pintype "bidirectional"))
    )
    (net (code "5") (name "A_SPI_NSS") (class "Default")
      (node (ref "ATMEGA328P") (pin "14") (pinfunction "PB2(SS/OC1B)_14") (pintype "bidirectional"))
      (node (ref "TXB0104") (pin "10") (pinfunction "B4_10") (pintype "bidirectional"))
    )
    (net (code "6") (name "A_SPI_SCLK") (class "Default")
      (node (ref "ATMEGA328P") (pin "17") (pinfunction "PB5(SCK)_17") (pintype "bidirectional"))
      (node (ref "ICSP") (pin "3") (pinfunction "SCK_3") (pintype "output"))
      (node (ref "TXB0104") (pin "13") (pinfunction "B1_13") (pintype "bidirectional"))
    )
    (net (code "7") (name "BATTSENS") (class "Default")
      (node (ref "JP8") (pin "1") (pinfunction "1_1") (pintype "passive"))
      (node (ref "STM32F722") (pin "22") (pinfunction "PA6_22") (pintype "bidirectional"))
    )
    (net (code "8") (name "B_SPI_MISO") (class "Default")
      (node (ref "BMP280") (pin "5") (pinfunction "SDO_5") (pintype "input"))
      (node (ref "TXB0104") (pin "3") (pinfunction "A2_3") (pintype "bidirectional"))
    )
    (net (code "9") (name "B_SPI_MOSI") (class "Default")
      (node (ref "BMP280") (pin "3") (pinfunction "SDI_3") (pintype "bidirectional"))
      (node (ref "TXB0104") (pin "4") (pinfunction "A3_4") (pintype "bidirectional"))
    )
    (net (code "10") (name "B_SPI_NSS") (class "Default")
      (node (ref "BMP280") (pin "2") (pinfunction "CSB_2") (pintype "input"))
      (node (ref "TXB0104") (pin "5") (pinfunction "A4_5") (pintype "bidirectional"))
    )
    (net (code "11") (name "B_SPI_SCLK") (class "Default")
      (node (ref "BMP280") (pin "4") (pinfunction "SCK_4") (pintype "bidirectional"))
      (node (ref "TXB0104") (pin "2") (pinfunction "A1_2") (pintype "bidirectional"))
    )
    (net (code "12") (name "CE") (class "Default")
      (node (ref "NRF24L01") (pin "CE") (pinfunction "CE_CE") (pintype "bidirectional"))
      (node (ref "STM32F722") (pin "37") (pinfunction "PC6_37") (pintype "bidirectional"))
    )
    (net (code "13") (name "DAC_OUT") (class "Default")
      (node (ref "DAC") (pin "1") (pinfunction "1_1") (pintype "passive"))
      (node (ref "STM32F722") (pin "21") (pinfunction "PA5_21") (pintype "bidirectional"))
    )
    (net (code "14") (name "DRDY") (class "Default")
      (node (ref "GY87") (pin "1") (pinfunction "1_1") (pintype "passive"))
    )
    (net (code "15") (name "ECHO1_IN") (class "Default")
      (node (ref "ATMEGA328P") (pin "31") (pinfunction "PD1(TXD)_31") (pintype "bidirectional"))
      (node (ref "SONIC1") (pin "3") (pinfunction "3_3") (pintype "bidirectional"))
    )
    (net (code "16") (name "ECHO2_IN") (class "Default")
      (node (ref "ATMEGA328P") (pin "24") (pinfunction "PC1(ADC1)_24") (pintype "bidirectional"))
      (node (ref "SONIC2") (pin "3") (pinfunction "3_3") (pintype "bidirectional"))
    )
    (net (code "17") (name "EPX_PAD") (class "Default")
      (node (ref "ICM20689") (pin "25") (pinfunction "EPX_PAD_25") (pintype "power_in"))
    )
    (net (code "18") (name "FSYNC") (class "Default")
      (node (ref "GY87") (pin "3") (pinfunction "3_3") (pintype "passive"))
    )
    (net (code "19") (name "GIMBAL_X") (class "Default")
      (node (ref "GIMBAL_X") (pin "1") (pinfunction "1_1") (pintype "passive"))
      (node (ref "STM32F722") (pin "56") (pinfunction "PB4_56") (pintype "bidirectional"))
    )
    (net (code "20") (name "GIMBAL_Y") (class "Default")
      (node (ref "GIMBAL_Y") (pin "1") (pinfunction "1_1") (pintype "passive"))
      (node (ref "STM32F722") (pin "57") (pinfunction "PB5_57") (pintype "bidirectional"))
    )
    (net (code "21") (name "GIMBAL_Z") (class "Default")
      (node (ref "GIMBAL_Z") (pin "1") (pinfunction "1_1") (pintype "passive"))
      (node (ref "STM32F722") (pin "25") (pinfunction "PB0_25") (pintype "bidirectional"))
    )
    (net (code "22") (name "GND") (class "Default")
      (node (ref "ADC1") (pin "3") (pinfunction "3_3") (pintype "passive"))
      (node (ref "ADC2") (pin "3") (pinfunction "3_3") (pintype "passive"))
      (node (ref "ATMEGA328P") (pin "21") (pinfunction "AGND_21") (pintype "bidirectional"))
      (node (ref "ATMEGA328P") (pin "3") (pinfunction "GND_3") (pintype "bidirectional"))
      (node (ref "ATMEGA328P") (pin "5") (pinfunction "GND_5") (pintype "bidirectional"))
      (node (ref "BATT_SENS") (pin "1") (pinfunction "1_1") (pintype "passive"))
      (node (ref "BMP280") (pin "1") (pinfunction "GND_1") (pintype "power_in"))
      (node (ref "BMP280") (pin "7") (pinfunction "GND_7") (pintype "power_in"))
      (node (ref "C1") (pin "2") (pinfunction "2_2") (pintype "passive"))
      (node (ref "C10") (pin "1") (pinfunction "1_1") (pintype "passive"))
      (node (ref "C11") (pin "1") (pinfunction "1_1") (pintype "passive"))
      (node (ref "C12") (pin "2") (pinfunction "2_2") (pintype "passive"))
      (node (ref "C13") (pin "2") (pinfunction "2_2") (pintype "passive"))
      (node (ref "C14") (pin "2") (pinfunction "2_2") (pintype "passive"))
      (node (ref "C15") (pin "2") (pinfunction "2_2") (pintype "passive"))
      (node (ref "C16") (pin "2") (pinfunction "2_2") (pintype "passive"))
      (node (ref "C17") (pin "2") (pinfunction "2_2") (pintype "passive"))
      (node (ref "C18") (pin "2") (pinfunction "2_2") (pintype "passive"))
      (node (ref "C19") (pin "2") (pinfunction "2_2") (pintype "passive"))
      (node (ref "C2") (pin "2") (pinfunction "2_2") (pintype "passive"))
      (node (ref "C20") (pin "2") (pinfunction "2_2") (pintype "passive"))
      (node (ref "C21") (pin "2") (pinfunction "2_2") (pintype "passive"))
      (node (ref "C22") (pin "2") (pinfunction "2_2") (pintype "passive"))
      (node (ref "C23") (pin "2") (pinfunction "2_2") (pintype "passive"))
      (node (ref "C27") (pin "2") (pinfunction "2_2") (pintype "passive"))
      (node (ref "C28") (pin "1") (pinfunction "1_1") (pintype "passive"))
      (node (ref "C29") (pin "1") (pinfunction "1_1") (pintype "passive"))
      (node (ref "C3") (pin "2") (pinfunction "2_2") (pintype "passive"))
      (node (ref "C30") (pin "2") (pinfunction "2_2") (pintype "passive"))
      (node (ref "C32") (pin "2") (pinfunction "2_2") (pintype "passive"))
      (node (ref "C33") (pin "2") (pinfunction "2_2") (pintype "passive"))
      (node (ref "C34") (pin "2") (pinfunction "2_2") (pintype "passive"))
      (node (ref "C35") (pin "2") (pinfunction "2_2") (pintype "passive"))
      (node (ref "C36") (pin "1") (pinfunction "1_1") (pintype "passive"))
      (node (ref "C37") (pin "1") (pinfunction "1_1") (pintype "passive"))
      (node (ref "C38") (pin "1") (pinfunction "1_1") (pintype "passive"))
      (node (ref "C39") (pin "1") (pinfunction "1_1") (pintype "passive"))
      (node (ref "C4") (pin "2") (pinfunction "2_2") (pintype "passive"))
      (node (ref "C40") (pin "2") (pinfunction "2_2") (pintype "passive"))
      (node (ref "C41") (pin "1") (pinfunction "1_1") (pintype "passive"))
      (node (ref "C42") (pin "1") (pinfunction "1_1") (pintype "passive"))
      (node (ref "C5") (pin "2") (pinfunction "2_2") (pintype "passive"))
      (node (ref "C6") (pin "2") (pinfunction "2_2") (pintype "passive"))
      (node (ref "C7") (pin "2") (pinfunction "2_2") (pintype "passive"))
      (node (ref "C8") (pin "2") (pinfunction "2_2") (pintype "passive"))
      (node (ref "C9") (pin "2") (pinfunction "2_2") (pintype "passive"))
      (node (ref "DAC") (pin "3") (pinfunction "3_3") (pintype "passive"))
      (node (ref "FT232RL") (pin "18") (pinfunction "GND_18") (pintype "power_in"))
      (node (ref "FT232RL") (pin "21") (pinfunction "GND_21") (pintype "power_in"))
      (node (ref "FT232RL") (pin "25") (pinfunction "GND_25") (pintype "power_in"))
      (node (ref "FT232RL") (pin "26") (pinfunction "TEST_26") (pintype "input"))
      (node (ref "FT232RL") (pin "7") (pinfunction "GND_7") (pintype "power_in"))
      (node (ref "GIMBAL_X") (pin "3") (pinfunction "3_3") (pintype "passive"))
      (node (ref "GIMBAL_Y") (pin "3") (pinfunction "3_3") (pintype "passive"))
      (node (ref "GIMBAL_Z") (pin "3") (pinfunction "3_3") (pintype "passive"))
      (node (ref "GPS") (pin "2") (pinfunction "2_2") (pintype "bidirectional"))
      (node (ref "GY87") (pin "6") (pinfunction "6_6") (pintype "passive"))
      (node (ref "ICM20689") (pin "11") (pinfunction "FSYNC_11") (pintype "input"))
      (node (ref "ICM20689") (pin "18") (pinfunction "GND_18") (pintype "power_in"))
      (node (ref "ICSP") (pin "6") (pinfunction "GND_6") (pintype "power_in"))
      (node (ref "JTAG") (pin "3") (pinfunction "3_3") (pintype "passive"))
      (node (ref "LED") (pin "3") (pinfunction "3_3") (pintype "passive"))
      (node (ref "LM3940-3.3") (pin "2") (pinfunction "GND_2_2") (pintype "passive"))
      (node (ref "LM3940-3.3") (pin "4") (pinfunction "GND_4") (pintype "passive"))
      (node (ref "M1") (pin "3") (pinfunction "3_3") (pintype "passive"))
      (node (ref "M2") (pin "3") (pinfunction "3_3") (pintype "passive"))
      (node (ref "M3") (pin "3") (pinfunction "3_3") (pintype "passive"))
      (node (ref "M4") (pin "3") (pinfunction "3_3") (pintype "passive"))
      (node (ref "NRF24L01") (pin "GND") (pinfunction "GND_GND") (pintype "power_in"))
      (node (ref "OSD") (pin "2") (pinfunction "2_2") (pintype "bidirectional"))
      (node (ref "OSD/USB") (pin "3") (pinfunction "3_3") (pintype "passive"))
      (node (ref "PPM") (pin "3") (pinfunction "3_3") (pintype "passive"))
      (node (ref "R1") (pin "1") (pinfunction "1_1") (pintype "passive"))
      (node (ref "R10") (pin "1") (pinfunction "1_1") (pintype "passive"))
      (node (ref "R11") (pin "1") (pinfunction "1_1") (pintype "passive"))
      (node (ref "R12") (pin "1") (pinfunction "1_1") (pintype "passive"))
      (node (ref "R6") (pin "1") (pinfunction "1_1") (pintype "passive"))
      (node (ref "R9") (pin "1") (pinfunction "1_1") (pintype "passive"))
      (node (ref "RESET") (pin "P$2") (pinfunction "P$2_P$2") (pintype "passive"))
      (node (ref "SD_CARD") (pin "6") (pinfunction "VSS_6") (pintype "power_in"))
      (node (ref "SONIC1") (pin "4") (pinfunction "4_4") (pintype "bidirectional"))
      (node (ref "SONIC2") (pin "4") (pinfunction "4_4") (pintype "bidirectional"))
      (node (ref "STM32F722") (pin "12") (pinfunction "VSSA_12") (pintype "power_in"))
      (node (ref "STM32F722") (pin "18") (pinfunction "VSS_2_18") (pintype "power_in"))
      (node (ref "STM32F722") (pin "31") (pinfunction "VSS_3_31") (pintype "power_in"))
      (node (ref "STM32F722") (pin "47") (pinfunction "VSS_4_47") (pintype "power_in"))
      (node (ref "STM32F722") (pin "63") (pinfunction "VSS_63") (pintype "power_in"))
      (node (ref "TXB0104") (pin "7") (pinfunction "GND_7") (pintype "bidirectional"))
      (node (ref "USB") (pin "GND") (pinfunction "GND_GND") (pintype "power_in"))
      (node (ref "USB") (pin "MT1") (pinfunction "SHIELD_MT1") (pintype "bidirectional"))
      (node (ref "USB") (pin "MT2") (pinfunction "SHIELD_MT2") (pintype "bidirectional"))
      (node (ref "USB") (pin "P$1") (pinfunction "SHIELD_P$1") (pintype "bidirectional"))
      (node (ref "USB") (pin "P$2") (pinfunction "SHIELD_P$2") (pintype "bidirectional"))
    )
    (net (code "23") (name "I2C1_SCL") (class "Default")
      (node (ref "GY87") (pin "5") (pinfunction "5_5") (pintype "passive"))
      (node (ref "R4") (pin "1") (pinfunction "1_1") (pintype "passive"))
      (node (ref "STM32F722") (pin "58") (pinfunction "PB6_58") (pintype "bidirectional"))
    )
    (net (code "24") (name "I2C1_SDA") (class "Default")
      (node (ref "GY87") (pin "4") (pinfunction "4_4") (pintype "passive"))
      (node (ref "R5") (pin "1") (pinfunction "1_1") (pintype "passive"))
      (node (ref "STM32F722") (pin "59") (pinfunction "PB7_59") (pintype "bidirectional"))
    )
    (net (code "25") (name "I2C2_SCL") (class "Default")
      (node (ref "ATMEGA328P") (pin "28") (pinfunction "PC5(ADC5/SCL)_28") (pintype "bidirectional"))
      (node (ref "R3") (pin "1") (pinfunction "1_1") (pintype "passive"))
      (node (ref "STM32F722") (pin "41") (pinfunction "PA8_41") (pintype "bidirectional"))
    )
    (net (code "26") (name "I2C2_SDA") (class "Default")
      (node (ref "ATMEGA328P") (pin "27") (pinfunction "PC4(ADC4/SDA)_27") (pintype "bidirectional"))
      (node (ref "R2") (pin "1") (pinfunction "1_1") (pintype "passive"))
      (node (ref "STM32F722") (pin "40") (pinfunction "PC9_40") (pintype "bidirectional"))
    )
    (net (code "27") (name "IMU_INT") (class "Default")
      (node (ref "ICM20689") (pin "12") (pinfunction "INT_12") (pintype "output"))
      (node (ref "STM32F722") (pin "62") (pinfunction "PB9_62") (pintype "bidirectional"))
    )
    (net (code "28") (name "INIT_OK") (class "Default")
      (node (ref "LED5") (pin "A") (pinfunction "A_A") (pintype "passive"))
      (node (ref "STM32F722") (pin "23") (pinfunction "PA7_23") (pintype "bidirectional"))
    )
    (net (code "29") (name "INTA") (class "Default")
      (node (ref "GY87") (pin "2") (pinfunction "2_2") (pintype "passive"))
      (node (ref "STM32F722") (pin "61") (pinfunction "PB8_61") (pintype "bidirectional"))
    )
    (net (code "30") (name "IRQ") (class "Default")
      (node (ref "NRF24L01") (pin "IRQ") (pinfunction "IRQ_IRQ") (pintype "bidirectional"))
      (node (ref "STM32F722") (pin "38") (pinfunction "PC7_38") (pintype "bidirectional"))
    )
    (net (code "31") (name "LED") (class "Default")
      (node (ref "ATMEGA328P") (pin "13") (pinfunction "PB1(OC1A)_13") (pintype "bidirectional"))
      (node (ref "LED") (pin "2") (pinfunction "2_2") (pintype "passive"))
    )
    (net (code "32") (name "LED_RX") (class "Default")
      (node (ref "FT232RL") (pin "23") (pinfunction "CBUS0_23") (pintype "bidirectional"))
      (node (ref "R8") (pin "1") (pinfunction "1_1") (pintype "passive"))
    )
    (net (code "33") (name "LED_TX") (class "Default")
      (node (ref "FT232RL") (pin "22") (pinfunction "CBUS1_22") (pintype "bidirectional"))
      (node (ref "R7") (pin "1") (pinfunction "1_1") (pintype "passive"))
    )
    (net (code "34") (name "LLVOE") (class "Default")
      (node (ref "R1") (pin "2") (pinfunction "2_2") (pintype "passive"))
      (node (ref "STM32F722") (pin "44") (pinfunction "PA11_44") (pintype "bidirectional"))
      (node (ref "TXB0104") (pin "8") (pinfunction "OE_8") (pintype "bidirectional"))
    )
    (net (code "35") (name "MOD0_LED") (class "Default")
      (node (ref "LED3") (pin "A") (pinfunction "A_A") (pintype "passive"))
      (node (ref "STM32F722") (pin "24") (pinfunction "PC4_24") (pintype "bidirectional"))
    )
    (net (code "36") (name "MOD1_LED") (class "Default")
      (node (ref "LED4") (pin "A") (pinfunction "A_A") (pintype "passive"))
      (node (ref "STM32F722") (pin "26") (pinfunction "PB1_26") (pintype "bidirectional"))
    )
    (net (code "37") (name "Net-(ATMEGA328P-AREF)") (class "Default")
      (node (ref "ATMEGA328P") (pin "20") (pinfunction "AREF_20") (pintype "bidirectional"))
      (node (ref "C12") (pin "1") (pinfunction "1_1") (pintype "passive"))
    )
    (net (code "38") (name "Net-(ATMEGA328P-PB6(XTAL1{slash}TOSC1))") (class "Default")
      (node (ref "ATMEGA328P") (pin "7") (pinfunction "PB6(XTAL1/TOSC1)_7") (pintype "bidirectional"))
      (node (ref "C10") (pin "2") (pinfunction "2_2") (pintype "passive"))
      (node (ref "Y2") (pin "3") (pinfunction "2_3") (pintype "passive"))
    )
    (net (code "39") (name "Net-(ATMEGA328P-PB7(XTAL2{slash}TOSC2))") (class "Default")
      (node (ref "ATMEGA328P") (pin "8") (pinfunction "PB7(XTAL2/TOSC2)_8") (pintype "bidirectional"))
      (node (ref "C11") (pin "2") (pinfunction "2_2") (pintype "passive"))
      (node (ref "Y2") (pin "1") (pinfunction "1_1") (pintype "passive"))
    )
    (net (code "40") (name "Net-(FT232RL-3V3OUT)") (class "Default")
      (node (ref "C36") (pin "2") (pinfunction "2_2") (pintype "passive"))
      (node (ref "FT232RL") (pin "17") (pinfunction "3V3OUT_17") (pintype "output"))
    )
    (net (code "41") (name "Net-(FT232RL-~{DTR})") (class "Default")
      (node (ref "C31") (pin "1") (pinfunction "1_1") (pintype "passive"))
      (node (ref "FT232RL") (pin "2") (pinfunction "~{DTR}_2") (pintype "output"))
    )
    (net (code "42") (name "Net-(ICM20689-REGOUT)") (class "Default")
      (node (ref "C39") (pin "2") (pinfunction "2_2") (pintype "passive"))
      (node (ref "ICM20689") (pin "10") (pinfunction "REGOUT_10") (pintype "output"))
    )
    (net (code "43") (name "Net-(LED1-PadC)") (class "Default")
      (node (ref "LED1") (pin "C") (pinfunction "C_C") (pintype "passive"))
      (node (ref "R7") (pin "2") (pinfunction "2_2") (pintype "passive"))
    )
    (net (code "44") (name "Net-(LED2-PadC)") (class "Default")
      (node (ref "LED2") (pin "C") (pinfunction "C_C") (pintype "passive"))
      (node (ref "R8") (pin "2") (pinfunction "2_2") (pintype "passive"))
    )
    (net (code "45") (name "Net-(LED3-PadC)") (class "Default")
      (node (ref "LED3") (pin "C") (pinfunction "C_C") (pintype "passive"))
      (node (ref "R9") (pin "2") (pinfunction "2_2") (pintype "passive"))
    )
    (net (code "46") (name "Net-(LED4-PadC)") (class "Default")
      (node (ref "LED4") (pin "C") (pinfunction "C_C") (pintype "passive"))
      (node (ref "R10") (pin "2") (pinfunction "2_2") (pintype "passive"))
    )
    (net (code "47") (name "Net-(LED5-PadC)") (class "Default")
      (node (ref "LED5") (pin "C") (pinfunction "C_C") (pintype "passive"))
      (node (ref "R11") (pin "2") (pinfunction "2_2") (pintype "passive"))
    )
    (net (code "48") (name "Net-(LED6-PadC)") (class "Default")
      (node (ref "LED6") (pin "C") (pinfunction "C_C") (pintype "passive"))
      (node (ref "R12") (pin "2") (pinfunction "2_2") (pintype "passive"))
    )
    (net (code "49") (name "Net-(STM32F722A-BOOT0)") (class "Default")
      (node (ref "R6") (pin "2") (pinfunction "2_2") (pintype "passive"))
      (node (ref "STM32F722") (pin "60") (pinfunction "BOOT0_60") (pintype "input"))
    )
    (net (code "50") (name "Net-(STM32F722A-PH0-OSC_IN)") (class "Default")
      (node (ref "C8") (pin "1") (pinfunction "1_1") (pintype "passive"))
      (node (ref "STM32F722") (pin "5") (pinfunction "PH0-OSC_IN_5") (pintype "bidirectional"))
      (node (ref "Y1") (pin "3") (pinfunction "2_3") (pintype "passive"))
    )
    (net (code "51") (name "Net-(STM32F722A-PH1-OSC_OUT)") (class "Default")
      (node (ref "C9") (pin "1") (pinfunction "1_1") (pintype "passive"))
      (node (ref "STM32F722") (pin "6") (pinfunction "PH1-OSC_OUT_6") (pintype "bidirectional"))
      (node (ref "Y1") (pin "1") (pinfunction "1_1") (pintype "passive"))
    )
    (net (code "52") (name "Net-(STM32F722B-VCAP_1)") (class "Default")
      (node (ref "C1") (pin "1") (pinfunction "1_1") (pintype "passive"))
      (node (ref "STM32F722") (pin "30") (pinfunction "VCAP_1_30") (pintype "power_in"))
    )
    (net (code "53") (name "PPM_IN") (class "Default")
      (node (ref "ATMEGA328P") (pin "32") (pinfunction "PD2(INT0)_32") (pintype "bidirectional"))
      (node (ref "PPM") (pin "1") (pinfunction "1_1") (pintype "passive"))
    )
    (net (code "54") (name "PWM_1") (class "Default")
      (node (ref "M1") (pin "1") (pinfunction "1_1") (pintype "passive"))
      (node (ref "STM32F722") (pin "14") (pinfunction "PA0-WKUP_14") (pintype "bidirectional"))
    )
    (net (code "55") (name "PWM_2") (class "Default")
      (node (ref "M2") (pin "1") (pinfunction "1_1") (pintype "passive"))
      (node (ref "STM32F722") (pin "15") (pinfunction "PA1_15") (pintype "bidirectional"))
    )
    (net (code "56") (name "PWM_3") (class "Default")
      (node (ref "M3") (pin "1") (pinfunction "1_1") (pintype "passive"))
      (node (ref "STM32F722") (pin "28") (pinfunction "PB10_28") (pintype "bidirectional"))
    )
    (net (code "57") (name "PWM_4") (class "Default")
      (node (ref "M4") (pin "1") (pinfunction "1_1") (pintype "passive"))
      (node (ref "STM32F722") (pin "29") (pinfunction "PB11_29") (pintype "bidirectional"))
    )
    (net (code "58") (name "RST") (class "Default")
      (node (ref "ATMEGA328P") (pin "29") (pinfunction "PC6(/RESET)_29") (pintype "bidirectional"))
      (node (ref "C30") (pin "1") (pinfunction "1_1") (pintype "passive"))
      (node (ref "C31") (pin "2") (pinfunction "2_2") (pintype "passive"))
      (node (ref "C35") (pin "1") (pinfunction "1_1") (pintype "passive"))
      (node (ref "ICSP") (pin "5") (pinfunction "RST_5") (pintype "output"))
      (node (ref "JTAG") (pin "5") (pinfunction "5_5") (pintype "passive"))
      (node (ref "R13") (pin "1") (pinfunction "1_1") (pintype "passive"))
      (node (ref "RESET") (pin "P$1") (pinfunction "P$1_P$1") (pintype "passive"))
      (node (ref "STM32F722") (pin "7") (pinfunction "NRST_7") (pintype "bidirectional"))
    )
    (net (code "59") (name "SD1_CK") (class "Default")
      (node (ref "SD_CARD") (pin "5") (pinfunction "CLK_5") (pintype "bidirectional"))
      (node (ref "STM32F722") (pin "53") (pinfunction "PC12_53") (pintype "bidirectional"))
    )
    (net (code "60") (name "SD1_CMD") (class "Default")
      (node (ref "SD_CARD") (pin "3") (pinfunction "CMD_3") (pintype "bidirectional"))
      (node (ref "STM32F722") (pin "54") (pinfunction "PD2_54") (pintype "bidirectional"))
    )
    (net (code "61") (name "SD1_D0") (class "Default")
      (node (ref "SD_CARD") (pin "7") (pinfunction "DAT0_7") (pintype "bidirectional"))
      (node (ref "STM32F722") (pin "39") (pinfunction "PC8_39") (pintype "bidirectional"))
    )
    (net (code "62") (name "SPI1_MISO") (class "Default")
      (node (ref "ICM20689") (pin "9") (pinfunction "AD0/SDO_9") (pintype "bidirectional"))
      (node (ref "STM32F722") (pin "52") (pinfunction "PC11_52") (pintype "bidirectional"))
    )
    (net (code "63") (name "SPI1_MOSI") (class "Default")
      (node (ref "ICM20689") (pin "24") (pinfunction "SDA/SDI_24") (pintype "bidirectional"))
      (node (ref "STM32F722") (pin "27") (pinfunction "PB2_27") (pintype "bidirectional"))
    )
    (net (code "64") (name "SPI1_NSS") (class "Default")
      (node (ref "ICM20689") (pin "22") (pinfunction "NCS_22") (pintype "input"))
      (node (ref "STM32F722") (pin "20") (pinfunction "PA4_20") (pintype "bidirectional"))
    )
    (net (code "65") (name "SPI1_SCLK") (class "Default")
      (node (ref "ICM20689") (pin "23") (pinfunction "SCL/SCLK_23") (pintype "input"))
      (node (ref "STM32F722") (pin "51") (pinfunction "PC10_51") (pintype "bidirectional"))
    )
    (net (code "66") (name "SPI2_MISO") (class "Default")
      (node (ref "NRF24L01") (pin "MISO") (pinfunction "MISO_MISO") (pintype "bidirectional"))
      (node (ref "STM32F722") (pin "10") (pinfunction "PC2_10") (pintype "bidirectional"))
    )
    (net (code "67") (name "SPI2_MOSI") (class "Default")
      (node (ref "NRF24L01") (pin "MOSI") (pinfunction "MOSI_MOSI") (pintype "bidirectional"))
      (node (ref "STM32F722") (pin "9") (pinfunction "PC1_9") (pintype "bidirectional"))
    )
    (net (code "68") (name "SPI2_NSS") (class "Default")
      (node (ref "NRF24L01") (pin "CSN") (pinfunction "CSN_CSN") (pintype "bidirectional"))
      (node (ref "STM32F722") (pin "33") (pinfunction "PB12_33") (pintype "bidirectional"))
    )
    (net (code "69") (name "SPI2_SCLK") (class "Default")
      (node (ref "NRF24L01") (pin "SCK") (pinfunction "SCK_SCK") (pintype "bidirectional"))
      (node (ref "STM32F722") (pin "34") (pinfunction "PB13_34") (pintype "bidirectional"))
    )
    (net (code "70") (name "SWCLK") (class "Default")
      (node (ref "JTAG") (pin "2") (pinfunction "2_2") (pintype "passive"))
      (node (ref "STM32F722") (pin "49") (pinfunction "PA14_49") (pintype "bidirectional"))
    )
    (net (code "71") (name "SWDIO") (class "Default")
      (node (ref "JTAG") (pin "4") (pinfunction "4_4") (pintype "passive"))
      (node (ref "STM32F722") (pin "46") (pinfunction "PA13_46") (pintype "bidirectional"))
    )
    (net (code "72") (name "SWO") (class "Default")
      (node (ref "JTAG") (pin "6") (pinfunction "6_6") (pintype "passive"))
      (node (ref "STM32F722") (pin "55") (pinfunction "PB3_55") (pintype "bidirectional"))
    )
    (net (code "73") (name "TRIGG1_IN") (class "Default")
      (node (ref "ATMEGA328P") (pin "30") (pinfunction "PD0(RXD)_30") (pintype "bidirectional"))
      (node (ref "SONIC1") (pin "2") (pinfunction "2_2") (pintype "bidirectional"))
    )
    (net (code "74") (name "TRIGG2_IN") (class "Default")
      (node (ref "ATMEGA328P") (pin "23") (pinfunction "PC0(ADC0)_23") (pintype "bidirectional"))
      (node (ref "SONIC2") (pin "2") (pinfunction "2_2") (pintype "bidirectional"))
    )
    (net (code "75") (name "UART1_RX") (class "Default")
      (node (ref "FT232RL") (pin "1") (pinfunction "TXD_1") (pintype "output"))
      (node (ref "OSD") (pin "3") (pinfunction "3_3") (pintype "bidirectional"))
      (node (ref "STM32F722") (pin "43") (pinfunction "PA10_43") (pintype "bidirectional"))
    )
    (net (code "76") (name "UART1_TX") (class "Default")
      (node (ref "FT232RL") (pin "5") (pinfunction "RXD_5") (pintype "input"))
      (node (ref "OSD") (pin "4") (pinfunction "4_4") (pintype "bidirectional"))
      (node (ref "STM32F722") (pin "42") (pinfunction "PA9_42") (pintype "bidirectional"))
    )
    (net (code "77") (name "UART2_RX") (class "Default")
      (node (ref "GPS") (pin "3") (pinfunction "3_3") (pintype "bidirectional"))
      (node (ref "STM32F722") (pin "17") (pinfunction "PA3_17") (pintype "bidirectional"))
    )
    (net (code "78") (name "UART2_TX") (class "Default")
      (node (ref "GPS") (pin "4") (pinfunction "4_4") (pintype "bidirectional"))
      (node (ref "STM32F722") (pin "16") (pinfunction "PA2_16") (pintype "bidirectional"))
    )
    (net (code "79") (name "USBDM") (class "Default")
      (node (ref "FT232RL") (pin "16") (pinfunction "USBDM_16") (pintype "bidirectional"))
      (node (ref "USB") (pin "D-") (pinfunction "D-_D-") (pintype "bidirectional"))
    )
    (net (code "80") (name "USBDP") (class "Default")
      (node (ref "FT232RL") (pin "15") (pinfunction "USBDP_15") (pintype "bidirectional"))
      (node (ref "USB") (pin "D+") (pinfunction "D+_D+") (pintype "bidirectional"))
    )
    (net (code "81") (name "USBOSD") (class "Default")
      (node (ref "OSD/USB") (pin "2") (pinfunction "2_2") (pintype "passive"))
      (node (ref "STM32F722") (pin "45") (pinfunction "PA12_45") (pintype "bidirectional"))
    )
    (net (code "82") (name "VBAT") (class "Default")
      (node (ref "STM32F722") (pin "1") (pinfunction "VBAT_1") (pintype "power_in"))
    )
    (net (code "83") (name "VCC") (class "Default")
      (node (ref "BMP280") (pin "6") (pinfunction "VDDIO_6") (pintype "power_in"))
      (node (ref "BMP280") (pin "8") (pinfunction "VDD_8") (pintype "power_in"))
      (node (ref "C16") (pin "1") (pinfunction "1_1") (pintype "passive"))
      (node (ref "C17") (pin "1") (pinfunction "1_1") (pintype "passive"))
      (node (ref "C19") (pin "1") (pinfunction "1_1") (pintype "passive"))
      (node (ref "C2") (pin "1") (pinfunction "1_1") (pintype "passive"))
      (node (ref "C20") (pin "1") (pinfunction "1_1") (pintype "passive"))
      (node (ref "C22") (pin "1") (pinfunction "1_1") (pintype "passive"))
      (node (ref "C27") (pin "1") (pinfunction "1_1") (pintype "passive"))
      (node (ref "C29") (pin "2") (pinfunction "2_2") (pintype "passive"))
      (node (ref "C3") (pin "1") (pinfunction "1_1") (pintype "passive"))
      (node (ref "C32") (pin "1") (pinfunction "1_1") (pintype "passive"))
      (node (ref "C33") (pin "1") (pinfunction "1_1") (pintype "passive"))
      (node (ref "C37") (pin "2") (pinfunction "2_2") (pintype "passive"))
      (node (ref "C38") (pin "2") (pinfunction "2_2") (pintype "passive"))
      (node (ref "C4") (pin "1") (pinfunction "1_1") (pintype "passive"))
      (node (ref "C40") (pin "1") (pinfunction "1_1") (pintype "passive"))
      (node (ref "C41") (pin "2") (pinfunction "2_2") (pintype "passive"))
      (node (ref "C42") (pin "2") (pinfunction "2_2") (pintype "passive"))
      (node (ref "C5") (pin "1") (pinfunction "1_1") (pintype "passive"))
      (node (ref "C6") (pin "1") (pinfunction "1_1") (pintype "passive"))
      (node (ref "C7") (pin "1") (pinfunction "1_1") (pintype "passive"))
      (node (ref "DAC") (pin "2") (pinfunction "2_2") (pintype "passive"))
      (node (ref "FT232RL") (pin "4") (pinfunction "VCCIO_4") (pintype "power_in"))
      (node (ref "GIMBAL_X") (pin "2") (pinfunction "2_2") (pintype "passive"))
      (node (ref "GIMBAL_Y") (pin "2") (pinfunction "2_2") (pintype "passive"))
      (node (ref "GIMBAL_Z") (pin "2") (pinfunction "2_2") (pintype "passive"))
      (node (ref "GPS") (pin "1") (pinfunction "1_1") (pintype "bidirectional"))
      (node (ref "GY87") (pin "7") (pinfunction "7_7") (pintype "passive"))
      (node (ref "ICM20689") (pin "13") (pinfunction "VDD_13") (pintype "power_in"))
      (node (ref "ICM20689") (pin "8") (pinfunction "VDDIO_8") (pintype "power_in"))
      (node (ref "JTAG") (pin "1") (pinfunction "1_1") (pintype "passive"))
      (node (ref "LED6") (pin "A") (pinfunction "A_A") (pintype "passive"))
      (node (ref "LM3940-3.3") (pin "3") (pinfunction "OUT_3") (pintype "output"))
      (node (ref "NRF24L01") (pin "VCC") (pinfunction "VCC_VCC") (pintype "power_in"))
      (node (ref "OSD") (pin "1") (pinfunction "1_1") (pintype "bidirectional"))
      (node (ref "OSD/USB") (pin "1") (pinfunction "1_1") (pintype "passive"))
      (node (ref "R13") (pin "2") (pinfunction "2_2") (pintype "passive"))
      (node (ref "R2") (pin "2") (pinfunction "2_2") (pintype "passive"))
      (node (ref "R3") (pin "2") (pinfunction "2_2") (pintype "passive"))
      (node (ref "R4") (pin "2") (pinfunction "2_2") (pintype "passive"))
      (node (ref "R5") (pin "2") (pinfunction "2_2") (pintype "passive"))
      (node (ref "SD_CARD") (pin "4") (pinfunction "VDD_4") (pintype "power_in"))
      (node (ref "STM32F722") (pin "13") (pinfunction "VDDA_13") (pintype "power_in"))
      (node (ref "STM32F722") (pin "19") (pinfunction "VDD_2_19") (pintype "power_in"))
      (node (ref "STM32F722") (pin "32") (pinfunction "VDD_3_32") (pintype "power_in"))
      (node (ref "STM32F722") (pin "48") (pinfunction "VDD_4_48") (pintype "power_in"))
      (node (ref "STM32F722") (pin "64") (pinfunction "VDD_64") (pintype "power_in"))
      (node (ref "TXB0104") (pin "1") (pinfunction "VCCA_1") (pintype "bidirectional"))
    )
    (net (code "84") (name "VCC_2") (class "Default")
      (node (ref "ADC1") (pin "2") (pinfunction "2_2") (pintype "passive"))
      (node (ref "ADC2") (pin "2") (pinfunction "2_2") (pintype "passive"))
      (node (ref "ATMEGA328P") (pin "18") (pinfunction "AVCC_18") (pintype "bidirectional"))
      (node (ref "ATMEGA328P") (pin "4") (pinfunction "VCC_4") (pintype "bidirectional"))
      (node (ref "ATMEGA328P") (pin "6") (pinfunction "VCC_6") (pintype "bidirectional"))
      (node (ref "C13") (pin "1") (pinfunction "1_1") (pintype "passive"))
      (node (ref "C14") (pin "1") (pinfunction "1_1") (pintype "passive"))
      (node (ref "C15") (pin "1") (pinfunction "1_1") (pintype "passive"))
      (node (ref "C18") (pin "1") (pinfunction "1_1") (pintype "passive"))
      (node (ref "C21") (pin "1") (pinfunction "1_1") (pintype "passive"))
      (node (ref "C23") (pin "1") (pinfunction "1_1") (pintype "passive"))
      (node (ref "C28") (pin "2") (pinfunction "2_2") (pintype "passive"))
      (node (ref "C34") (pin "1") (pinfunction "1_1") (pintype "passive"))
      (node (ref "D1") (pin "C") (pinfunction "C_C") (pintype "passive"))
      (node (ref "FT232RL") (pin "20") (pinfunction "VCC_20") (pintype "power_in"))
      (node (ref "ICSP") (pin "2") (pinfunction "VCC_2") (pintype "power_in"))
      (node (ref "LED") (pin "1") (pinfunction "1_1") (pintype "passive"))
      (node (ref "LED1") (pin "A") (pinfunction "A_A") (pintype "passive"))
      (node (ref "LED2") (pin "A") (pinfunction "A_A") (pintype "passive"))
      (node (ref "LM3940-3.3") (pin "1") (pinfunction "IN_1") (pintype "power_in"))
      (node (ref "M1") (pin "2") (pinfunction "2_2") (pintype "passive"))
      (node (ref "M2") (pin "2") (pinfunction "2_2") (pintype "passive"))
      (node (ref "M3") (pin "2") (pinfunction "2_2") (pintype "passive"))
      (node (ref "M4") (pin "2") (pinfunction "2_2") (pintype "passive"))
      (node (ref "PPM") (pin "2") (pinfunction "2_2") (pintype "passive"))
      (node (ref "SONIC1") (pin "1") (pinfunction "1_1") (pintype "bidirectional"))
      (node (ref "SONIC2") (pin "1") (pinfunction "1_1") (pintype "bidirectional"))
      (node (ref "TXB0104") (pin "14") (pinfunction "VCCB_14") (pintype "bidirectional"))
    )
    (net (code "85") (name "V_USB") (class "Default")
      (node (ref "D1") (pin "A") (pinfunction "A_A") (pintype "passive"))
      (node (ref "USB") (pin "VBUS") (pinfunction "VBUS_VBUS") (pintype "power_in"))
    )
    (net (code "86") (name "unconnected-(ATMEGA328P-PB0(ICP)-Pad12)") (class "Default")
      (node (ref "ATMEGA328P") (pin "12") (pinfunction "PB0(ICP)_12") (pintype "bidirectional"))
    )
    (net (code "87") (name "unconnected-(ATMEGA328P-PC2(ADC2)-Pad25)") (class "Default")
      (node (ref "ATMEGA328P") (pin "25") (pinfunction "PC2(ADC2)_25") (pintype "bidirectional"))
    )
    (net (code "88") (name "unconnected-(ATMEGA328P-PC3(ADC3)-Pad26)") (class "Default")
      (node (ref "ATMEGA328P") (pin "26") (pinfunction "PC3(ADC3)_26") (pintype "bidirectional"))
    )
    (net (code "89") (name "unconnected-(ATMEGA328P-PD3(INT1)-Pad1)") (class "Default")
      (node (ref "ATMEGA328P") (pin "1") (pinfunction "PD3(INT1)_1") (pintype "bidirectional"))
    )
    (net (code "90") (name "unconnected-(ATMEGA328P-PD4(XCK{slash}T0)-Pad2)") (class "Default")
      (node (ref "ATMEGA328P") (pin "2") (pinfunction "PD4(XCK/T0)_2") (pintype "bidirectional"))
    )
    (net (code "91") (name "unconnected-(ATMEGA328P-PD5(T1)-Pad9)") (class "Default")
      (node (ref "ATMEGA328P") (pin "9") (pinfunction "PD5(T1)_9") (pintype "bidirectional"))
    )
    (net (code "92") (name "unconnected-(ATMEGA328P-PD6(AIN0)-Pad10)") (class "Default")
      (node (ref "ATMEGA328P") (pin "10") (pinfunction "PD6(AIN0)_10") (pintype "bidirectional"))
    )
    (net (code "93") (name "unconnected-(ATMEGA328P-PD7(AIN1)-Pad11)") (class "Default")
      (node (ref "ATMEGA328P") (pin "11") (pinfunction "PD7(AIN1)_11") (pintype "bidirectional"))
    )
    (net (code "94") (name "unconnected-(FT232RL-CBUS2-Pad13)") (class "Default")
      (node (ref "FT232RL") (pin "13") (pinfunction "CBUS2_13") (pintype "bidirectional"))
    )
    (net (code "95") (name "unconnected-(FT232RL-CBUS3-Pad14)") (class "Default")
      (node (ref "FT232RL") (pin "14") (pinfunction "CBUS3_14") (pintype "bidirectional"))
    )
    (net (code "96") (name "unconnected-(FT232RL-CBUS4-Pad12)") (class "Default")
      (node (ref "FT232RL") (pin "12") (pinfunction "CBUS4_12") (pintype "bidirectional"))
    )
    (net (code "97") (name "unconnected-(FT232RL-OSCI-Pad27)") (class "Default")
      (node (ref "FT232RL") (pin "27") (pinfunction "OSCI_27") (pintype "input"))
    )
    (net (code "98") (name "unconnected-(FT232RL-OSCO-Pad28)") (class "Default")
      (node (ref "FT232RL") (pin "28") (pinfunction "OSCO_28") (pintype "output"))
    )
    (net (code "99") (name "unconnected-(FT232RL-~{CTS}-Pad11)") (class "Default")
      (node (ref "FT232RL") (pin "11") (pinfunction "~{CTS}_11") (pintype "input"))
    )
    (net (code "100") (name "unconnected-(FT232RL-~{DCD}-Pad10)") (class "Default")
      (node (ref "FT232RL") (pin "10") (pinfunction "~{DCD}_10") (pintype "input"))
    )
    (net (code "101") (name "unconnected-(FT232RL-~{DSR}-Pad9)") (class "Default")
      (node (ref "FT232RL") (pin "9") (pinfunction "~{DSR}_9") (pintype "input"))
    )
    (net (code "102") (name "unconnected-(FT232RL-~{RESET}-Pad19)") (class "Default")
      (node (ref "FT232RL") (pin "19") (pinfunction "~{RESET}_19") (pintype "input"))
    )
    (net (code "103") (name "unconnected-(FT232RL-~{RI}-Pad6)") (class "Default")
      (node (ref "FT232RL") (pin "6") (pinfunction "~{RI}_6") (pintype "input"))
    )
    (net (code "104") (name "unconnected-(FT232RL-~{RTS}-Pad3)") (class "Default")
      (node (ref "FT232RL") (pin "3") (pinfunction "~{RTS}_3") (pintype "output"))
    )
    (net (code "105") (name "unconnected-(GY87-Pad8)") (class "Default")
      (node (ref "GY87") (pin "8") (pinfunction "8_8") (pintype "passive"))
    )
    (net (code "106") (name "unconnected-(JP1-Pad1)") (class "Default")
      (node (ref "JP1") (pin "1") (pinfunction "1_1") (pintype "passive"))
    )
    (net (code "107") (name "unconnected-(JP1-Pad2)") (class "Default")
      (node (ref "JP1") (pin "2") (pinfunction "2_2") (pintype "passive"))
    )
    (net (code "108") (name "unconnected-(JP1-Pad3)") (class "Default")
      (node (ref "JP1") (pin "3") (pinfunction "3_3") (pintype "passive"))
    )
    (net (code "109") (name "unconnected-(JP1-Pad4)") (class "Default")
      (node (ref "JP1") (pin "4") (pinfunction "4_4") (pintype "passive"))
    )
    (net (code "110") (name "unconnected-(JP1-Pad5)") (class "Default")
      (node (ref "JP1") (pin "5") (pinfunction "5_5") (pintype "passive"))
    )
    (net (code "111") (name "unconnected-(JP1-Pad6)") (class "Default")
      (node (ref "JP1") (pin "6") (pinfunction "6_6") (pintype "passive"))
    )
    (net (code "112") (name "unconnected-(JP2-Pad1)") (class "Default")
      (node (ref "JP2") (pin "1") (pinfunction "1_1") (pintype "passive"))
    )
    (net (code "113") (name "unconnected-(JP2-Pad2)") (class "Default")
      (node (ref "JP2") (pin "2") (pinfunction "2_2") (pintype "passive"))
    )
    (net (code "114") (name "unconnected-(JP2-Pad3)") (class "Default")
      (node (ref "JP2") (pin "3") (pinfunction "3_3") (pintype "passive"))
    )
    (net (code "115") (name "unconnected-(JP2-Pad4)") (class "Default")
      (node (ref "JP2") (pin "4") (pinfunction "4_4") (pintype "passive"))
    )
    (net (code "116") (name "unconnected-(JP2-Pad5)") (class "Default")
      (node (ref "JP2") (pin "5") (pinfunction "5_5") (pintype "passive"))
    )
    (net (code "117") (name "unconnected-(JP2-Pad6)") (class "Default")
      (node (ref "JP2") (pin "6") (pinfunction "6_6") (pintype "passive"))
    )
    (net (code "118") (name "unconnected-(JP3-Pad1)") (class "Default")
      (node (ref "JP3") (pin "1") (pinfunction "1_1") (pintype "passive"))
    )
    (net (code "119") (name "unconnected-(JP3-Pad2)") (class "Default")
      (node (ref "JP3") (pin "2") (pinfunction "2_2") (pintype "passive"))
    )
    (net (code "120") (name "unconnected-(JP3-Pad3)") (class "Default")
      (node (ref "JP3") (pin "3") (pinfunction "3_3") (pintype "passive"))
    )
    (net (code "121") (name "unconnected-(JP3-Pad4)") (class "Default")
      (node (ref "JP3") (pin "4") (pinfunction "4_4") (pintype "passive"))
    )
    (net (code "122") (name "unconnected-(JP3-Pad5)") (class "Default")
      (node (ref "JP3") (pin "5") (pinfunction "5_5") (pintype "passive"))
    )
    (net (code "123") (name "unconnected-(JP3-Pad6)") (class "Default")
      (node (ref "JP3") (pin "6") (pinfunction "6_6") (pintype "passive"))
    )
    (net (code "124") (name "unconnected-(JP4-Pad1)") (class "Default")
      (node (ref "JP4") (pin "1") (pinfunction "1_1") (pintype "passive"))
    )
    (net (code "125") (name "unconnected-(JP4-Pad2)") (class "Default")
      (node (ref "JP4") (pin "2") (pinfunction "2_2") (pintype "passive"))
    )
    (net (code "126") (name "unconnected-(JP4-Pad3)") (class "Default")
      (node (ref "JP4") (pin "3") (pinfunction "3_3") (pintype "passive"))
    )
    (net (code "127") (name "unconnected-(JP4-Pad4)") (class "Default")
      (node (ref "JP4") (pin "4") (pinfunction "4_4") (pintype "passive"))
    )
    (net (code "128") (name "unconnected-(JP4-Pad5)") (class "Default")
      (node (ref "JP4") (pin "5") (pinfunction "5_5") (pintype "passive"))
    )
    (net (code "129") (name "unconnected-(JP4-Pad6)") (class "Default")
      (node (ref "JP4") (pin "6") (pinfunction "6_6") (pintype "passive"))
    )
    (net (code "130") (name "unconnected-(JP5-Pad1)") (class "Default")
      (node (ref "JP5") (pin "1") (pinfunction "1_1") (pintype "passive"))
    )
    (net (code "131") (name "unconnected-(JP5-Pad2)") (class "Default")
      (node (ref "JP5") (pin "2") (pinfunction "2_2") (pintype "passive"))
    )
    (net (code "132") (name "unconnected-(JP5-Pad3)") (class "Default")
      (node (ref "JP5") (pin "3") (pinfunction "3_3") (pintype "passive"))
    )
    (net (code "133") (name "unconnected-(JP5-Pad4)") (class "Default")
      (node (ref "JP5") (pin "4") (pinfunction "4_4") (pintype "passive"))
    )
    (net (code "134") (name "unconnected-(JP5-Pad5)") (class "Default")
      (node (ref "JP5") (pin "5") (pinfunction "5_5") (pintype "passive"))
    )
    (net (code "135") (name "unconnected-(JP5-Pad6)") (class "Default")
      (node (ref "JP5") (pin "6") (pinfunction "6_6") (pintype "passive"))
    )
    (net (code "136") (name "unconnected-(JP6-Pad1)") (class "Default")
      (node (ref "JP6") (pin "1") (pinfunction "1_1") (pintype "passive"))
    )
    (net (code "137") (name "unconnected-(JP6-Pad2)") (class "Default")
      (node (ref "JP6") (pin "2") (pinfunction "2_2") (pintype "passive"))
    )
    (net (code "138") (name "unconnected-(JP6-Pad3)") (class "Default")
      (node (ref "JP6") (pin "3") (pinfunction "3_3") (pintype "passive"))
    )
    (net (code "139") (name "unconnected-(JP6-Pad4)") (class "Default")
      (node (ref "JP6") (pin "4") (pinfunction "4_4") (pintype "passive"))
    )
    (net (code "140") (name "unconnected-(JP6-Pad5)") (class "Default")
      (node (ref "JP6") (pin "5") (pinfunction "5_5") (pintype "passive"))
    )
    (net (code "141") (name "unconnected-(JP6-Pad6)") (class "Default")
      (node (ref "JP6") (pin "6") (pinfunction "6_6") (pintype "passive"))
    )
    (net (code "142") (name "unconnected-(JP7-Pad1)") (class "Default")
      (node (ref "JP7") (pin "1") (pinfunction "1_1") (pintype "passive"))
    )
    (net (code "143") (name "unconnected-(JP7-Pad2)") (class "Default")
      (node (ref "JP7") (pin "2") (pinfunction "2_2") (pintype "passive"))
    )
    (net (code "144") (name "unconnected-(JP7-Pad3)") (class "Default")
      (node (ref "JP7") (pin "3") (pinfunction "3_3") (pintype "passive"))
    )
    (net (code "145") (name "unconnected-(JP7-Pad4)") (class "Default")
      (node (ref "JP7") (pin "4") (pinfunction "4_4") (pintype "passive"))
    )
    (net (code "146") (name "unconnected-(JP7-Pad5)") (class "Default")
      (node (ref "JP7") (pin "5") (pinfunction "5_5") (pintype "passive"))
    )
    (net (code "147") (name "unconnected-(JP7-Pad6)") (class "Default")
      (node (ref "JP7") (pin "6") (pinfunction "6_6") (pintype "passive"))
    )
    (net (code "148") (name "unconnected-(SD_CARD-DAT1-Pad8)") (class "Default")
      (node (ref "SD_CARD") (pin "8") (pinfunction "DAT1_8") (pintype "bidirectional"))
    )
    (net (code "149") (name "unconnected-(SD_CARD-DAT2-Pad1)") (class "Default")
      (node (ref "SD_CARD") (pin "1") (pinfunction "DAT2_1") (pintype "bidirectional"))
    )
    (net (code "150") (name "unconnected-(SD_CARD-DAT3{slash}CD-Pad2)") (class "Default")
      (node (ref "SD_CARD") (pin "2") (pinfunction "DAT3/CD_2") (pintype "bidirectional"))
    )
    (net (code "151") (name "unconnected-(STM32F722A-PA15-Pad50)") (class "Default")
      (node (ref "STM32F722") (pin "50") (pinfunction "PA15_50") (pintype "bidirectional"))
    )
    (net (code "152") (name "unconnected-(STM32F722A-PB14-Pad35)") (class "Default")
      (node (ref "STM32F722") (pin "35") (pinfunction "PB14_35") (pintype "bidirectional"))
    )
    (net (code "153") (name "unconnected-(STM32F722A-PB15-Pad36)") (class "Default")
      (node (ref "STM32F722") (pin "36") (pinfunction "PB15_36") (pintype "bidirectional"))
    )
    (net (code "154") (name "unconnected-(STM32F722A-PC0-Pad8)") (class "Default")
      (node (ref "STM32F722") (pin "8") (pinfunction "PC0_8") (pintype "bidirectional"))
    )
    (net (code "155") (name "unconnected-(STM32F722A-PC3-Pad11)") (class "Default")
      (node (ref "STM32F722") (pin "11") (pinfunction "PC3_11") (pintype "bidirectional"))
    )
    (net (code "156") (name "unconnected-(STM32F722A-PC13-Pad2)") (class "Default")
      (node (ref "STM32F722") (pin "2") (pinfunction "PC13_2") (pintype "bidirectional"))
    )
    (net (code "157") (name "unconnected-(STM32F722A-PC14-OSC32_IN-Pad3)") (class "Default")
      (node (ref "STM32F722") (pin "3") (pinfunction "PC14-OSC32_IN_3") (pintype "bidirectional"))
    )
    (net (code "158") (name "unconnected-(STM32F722A-PC15-OSC32_OUT-Pad4)") (class "Default")
      (node (ref "STM32F722") (pin "4") (pinfunction "PC15-OSC32_OUT_4") (pintype "bidirectional"))
    )
    (net (code "159") (name "unconnected-(USB-PadID)") (class "Default")
      (node (ref "USB") (pin "ID") (pinfunction "ID_ID") (pintype "bidirectional"))
    )
  )
)
